# SSPS_Front_Panel_Test.net
KiCad netlist of a schematic drawn in EAGLE
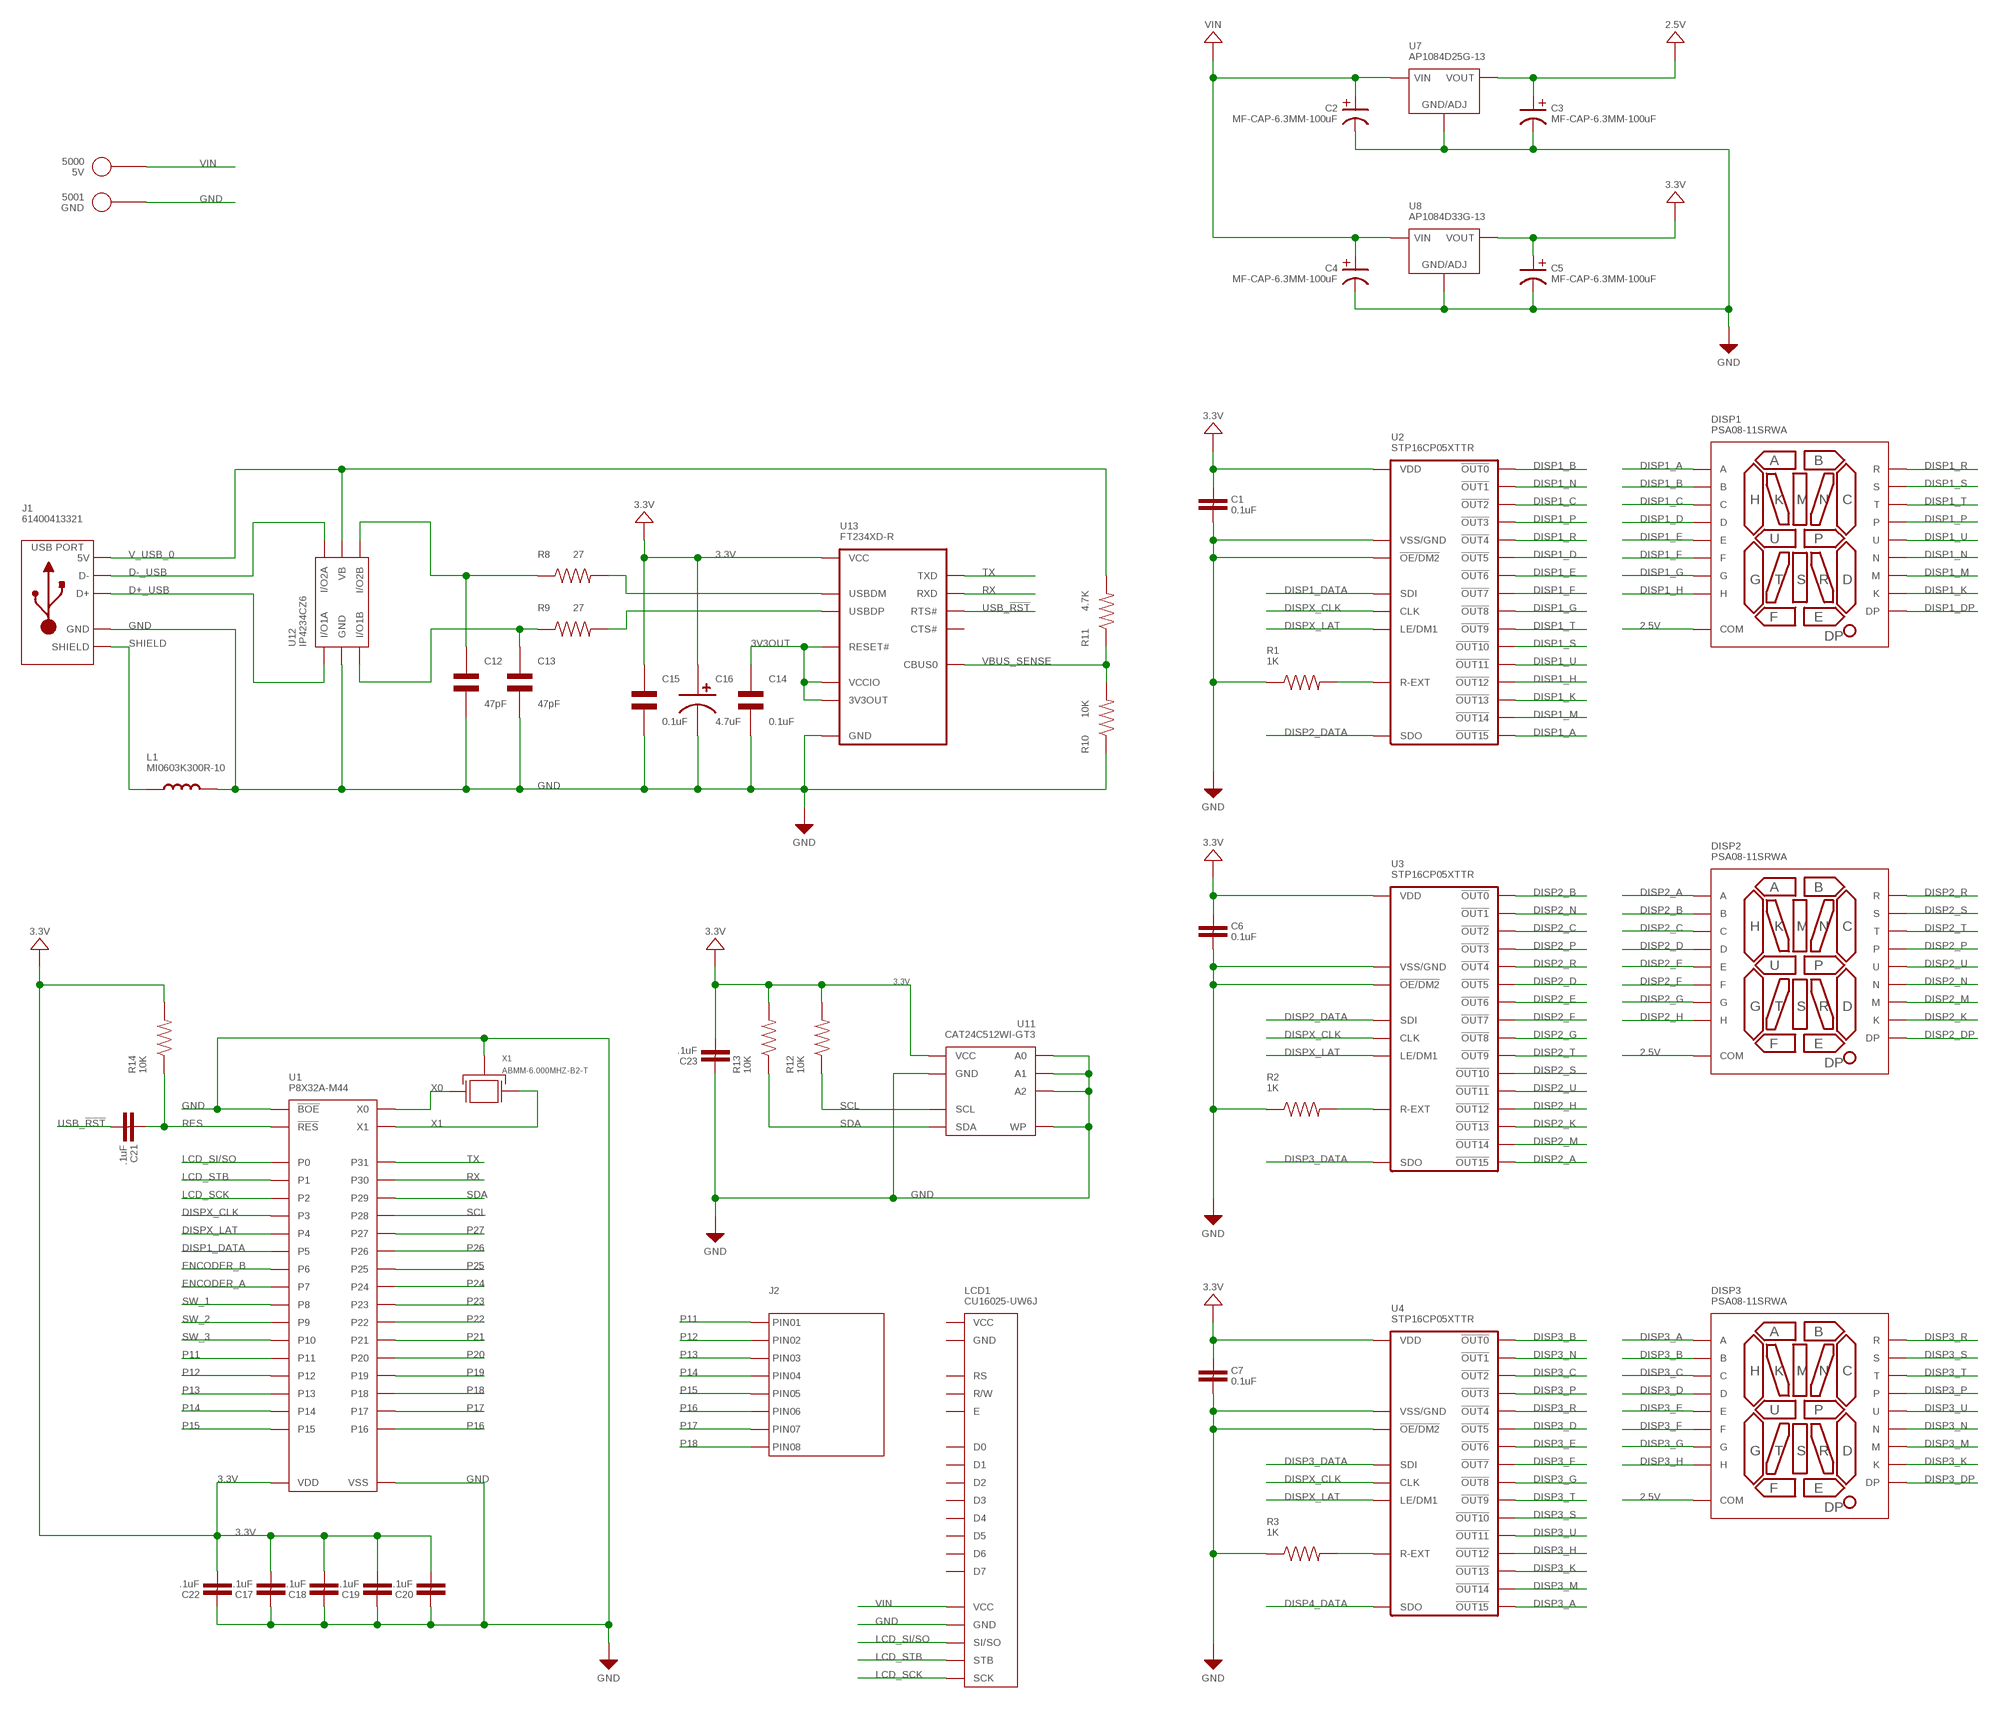
[diagram p0: schematic, sheet 1, part 1 of 3]
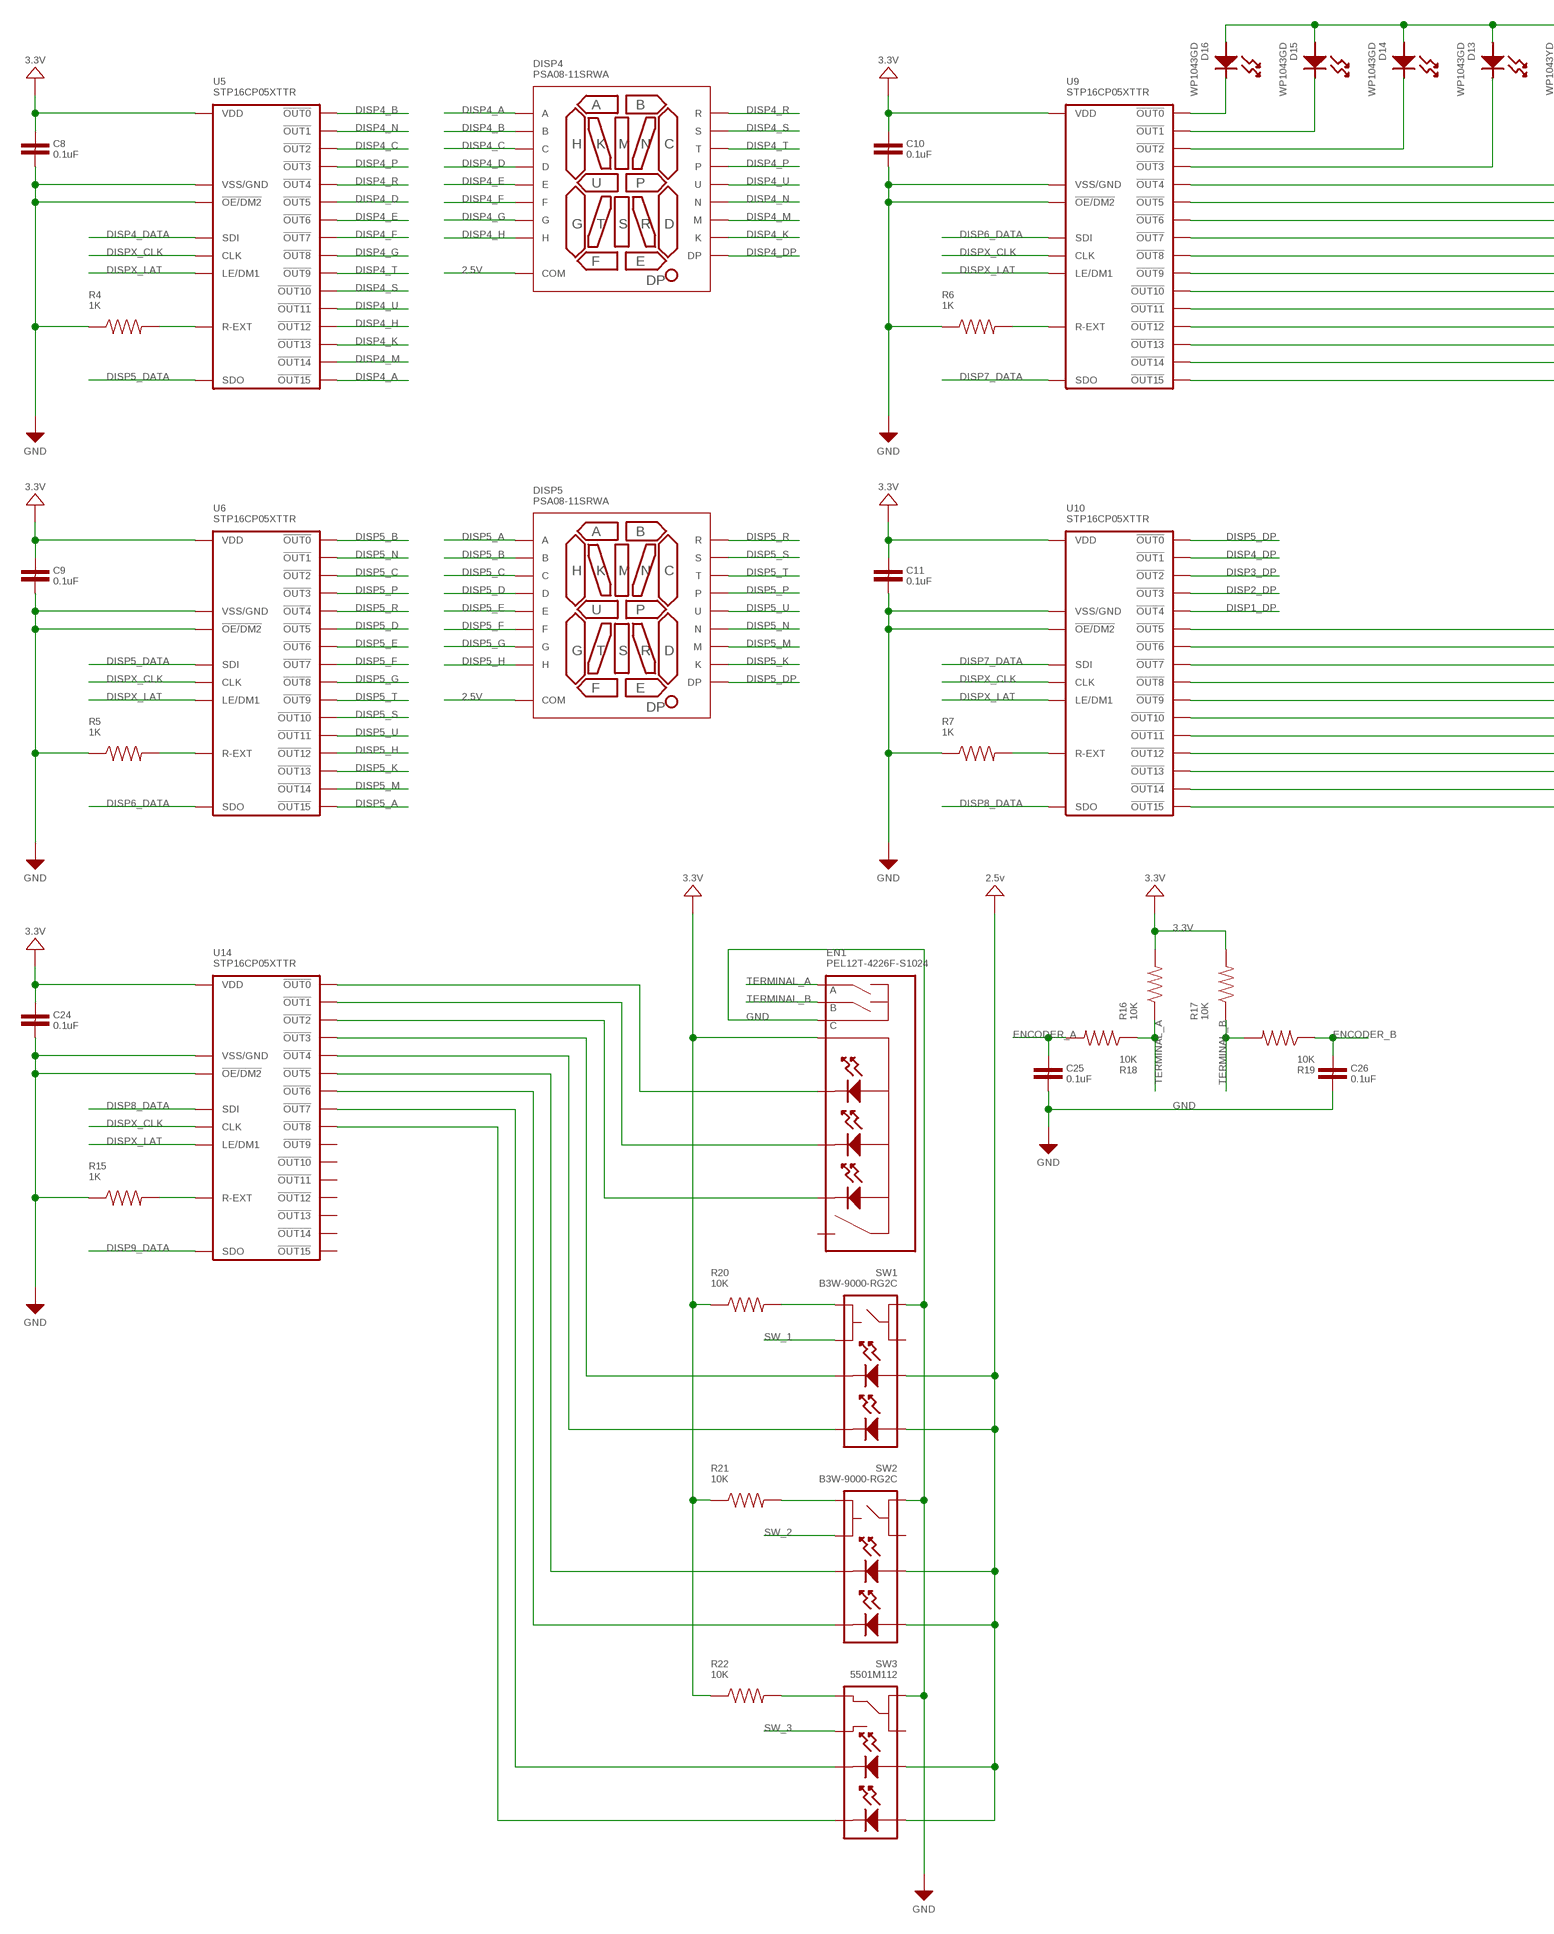
[diagram p1: schematic, sheet 1, part 2 of 3]
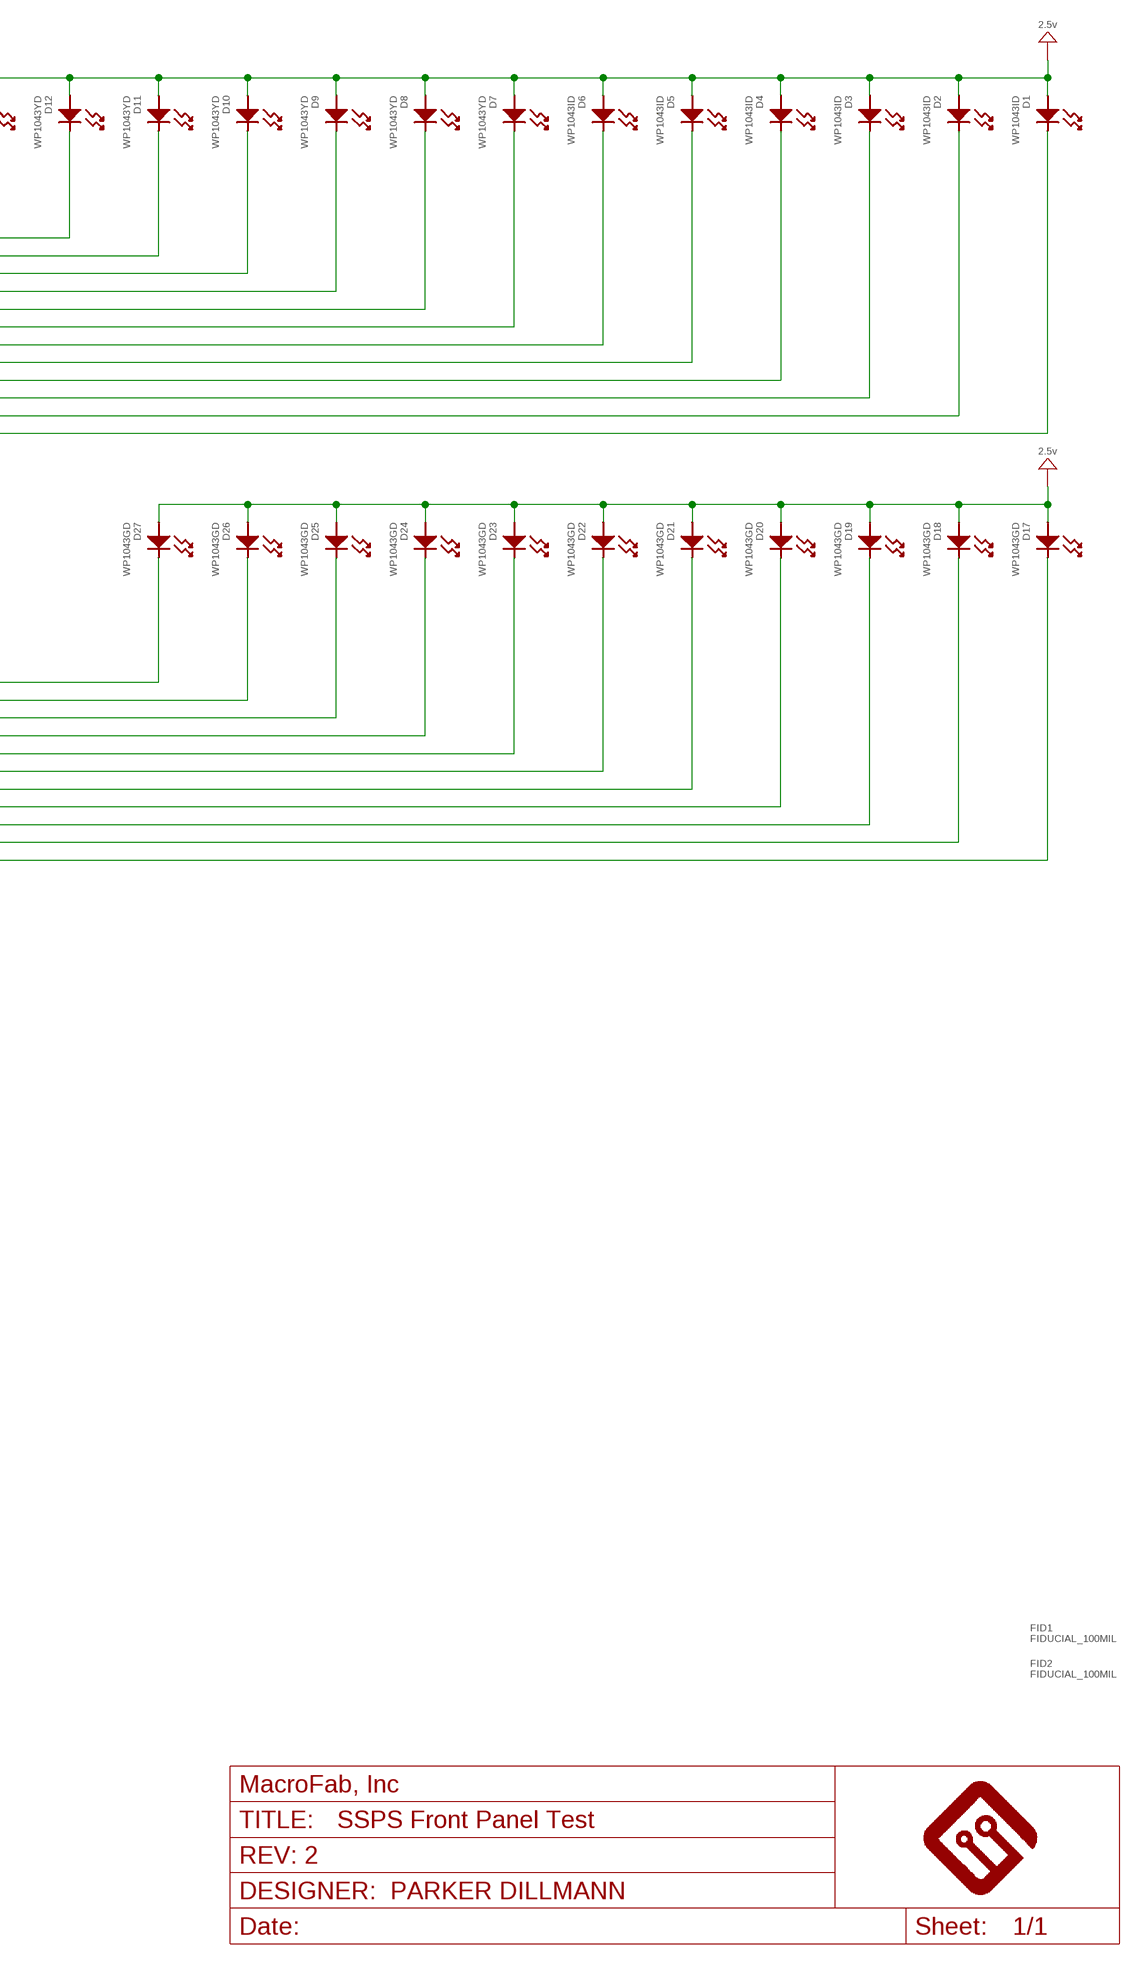
[diagram p2: schematic, sheet 1, part 3 of 3]

(export (version "E")
  (design (tool "Eeschema 10.0.6"))
  (components
    (comp (ref "5V")
      (value "5000")
      (footprint "eagle-import:KEYSTONE_5115-5119")
      (libsource (lib "eagle-import") (part "TEST_POINT_SINGLE_KEYSTONE_5115-5119"))
    )
    (comp (ref "C1")
      (value "0.1uF")
      (footprint "eagle-import:0603")
      (libsource (lib "eagle-import") (part "CAPACITOR_NON_POLAR_0603"))
    )
    (comp (ref "C2")
      (value "MF-CAP-6.3MM-100uF")
      (footprint "eagle-import:6.3MM_CAP_SMD")
      (libsource (lib "eagle-import") (part "CAPACITOR_POLARIZED_6.3MM_SMD"))
    )
    (comp (ref "C3")
      (value "MF-CAP-6.3MM-100uF")
      (footprint "eagle-import:6.3MM_CAP_SMD")
      (libsource (lib "eagle-import") (part "CAPACITOR_POLARIZED_6.3MM_SMD"))
    )
    (comp (ref "C4")
      (value "MF-CAP-6.3MM-100uF")
      (footprint "eagle-import:6.3MM_CAP_SMD")
      (libsource (lib "eagle-import") (part "CAPACITOR_POLARIZED_6.3MM_SMD"))
    )
    (comp (ref "C5")
      (value "MF-CAP-6.3MM-100uF")
      (footprint "eagle-import:6.3MM_CAP_SMD")
      (libsource (lib "eagle-import") (part "CAPACITOR_POLARIZED_6.3MM_SMD"))
    )
    (comp (ref "C6")
      (value "0.1uF")
      (footprint "eagle-import:0603")
      (libsource (lib "eagle-import") (part "CAPACITOR_NON_POLAR_0603"))
    )
    (comp (ref "C7")
      (value "0.1uF")
      (footprint "eagle-import:0603")
      (libsource (lib "eagle-import") (part "CAPACITOR_NON_POLAR_0603"))
    )
    (comp (ref "C8")
      (value "0.1uF")
      (footprint "eagle-import:0603")
      (libsource (lib "eagle-import") (part "CAPACITOR_NON_POLAR_0603"))
    )
    (comp (ref "C9")
      (value "0.1uF")
      (footprint "eagle-import:0603")
      (libsource (lib "eagle-import") (part "CAPACITOR_NON_POLAR_0603"))
    )
    (comp (ref "C10")
      (value "0.1uF")
      (footprint "eagle-import:0603")
      (libsource (lib "eagle-import") (part "CAPACITOR_NON_POLAR_0603"))
    )
    (comp (ref "C11")
      (value "0.1uF")
      (footprint "eagle-import:0603")
      (libsource (lib "eagle-import") (part "CAPACITOR_NON_POLAR_0603"))
    )
    (comp (ref "C12")
      (value "47pF")
      (footprint "eagle-import:C0603")
      (libsource (lib "eagle-import") (part "CAPACITOR_NP_0603"))
    )
    (comp (ref "C13")
      (value "47pF")
      (footprint "eagle-import:C0603")
      (libsource (lib "eagle-import") (part "CAPACITOR_NP_0603"))
    )
    (comp (ref "C14")
      (value "0.1uF")
      (footprint "eagle-import:C0603")
      (libsource (lib "eagle-import") (part "CAPACITOR_NP_0603"))
    )
    (comp (ref "C15")
      (value "0.1uF")
      (footprint "eagle-import:C0603")
      (libsource (lib "eagle-import") (part "CAPACITOR_NP_0603"))
    )
    (comp (ref "C16")
      (value "4.7uF")
      (footprint "eagle-import:CP4MM")
      (libsource (lib "eagle-import") (part "CAPACITOR_P_4MM"))
    )
    (comp (ref "C17")
      (value ".1uF")
      (footprint "eagle-import:0603")
      (libsource (lib "eagle-import") (part "CAPACITOR_NON_POLAR_0603"))
    )
    (comp (ref "C18")
      (value ".1uF")
      (footprint "eagle-import:0603")
      (libsource (lib "eagle-import") (part "CAPACITOR_NON_POLAR_0603"))
    )
    (comp (ref "C19")
      (value ".1uF")
      (footprint "eagle-import:0603")
      (libsource (lib "eagle-import") (part "CAPACITOR_NON_POLAR_0603"))
    )
    (comp (ref "C20")
      (value ".1uF")
      (footprint "eagle-import:0603")
      (libsource (lib "eagle-import") (part "CAPACITOR_NON_POLAR_0603"))
    )
    (comp (ref "C21")
      (value ".1uF")
      (footprint "eagle-import:0603")
      (libsource (lib "eagle-import") (part "CAPACITOR_NON_POLAR_0603"))
    )
    (comp (ref "C22")
      (value ".1uF")
      (footprint "eagle-import:0603")
      (libsource (lib "eagle-import") (part "CAPACITOR_NON_POLAR_0603"))
    )
    (comp (ref "C23")
      (value ".1uF")
      (footprint "eagle-import:0603")
      (libsource (lib "eagle-import") (part "CAPACITOR_NON_POLAR_0603"))
    )
    (comp (ref "C24")
      (value "0.1uF")
      (footprint "eagle-import:0603")
      (libsource (lib "eagle-import") (part "CAPACITOR_NON_POLAR_0603"))
    )
    (comp (ref "C25")
      (value "0.1uF")
      (footprint "eagle-import:0603")
      (libsource (lib "eagle-import") (part "CAPACITOR_NON_POLAR_0603"))
    )
    (comp (ref "C26")
      (value "0.1uF")
      (footprint "eagle-import:0603")
      (libsource (lib "eagle-import") (part "CAPACITOR_NON_POLAR_0603"))
    )
    (comp (ref "D1")
      (value "WP1043ID")
      (footprint "eagle-import:WP1043")
      (libsource (lib "eagle-import") (part "LED_SINGLE_WP1043"))
    )
    (comp (ref "D2")
      (value "WP1043ID")
      (footprint "eagle-import:WP1043")
      (libsource (lib "eagle-import") (part "LED_SINGLE_WP1043"))
    )
    (comp (ref "D3")
      (value "WP1043ID")
      (footprint "eagle-import:WP1043")
      (libsource (lib "eagle-import") (part "LED_SINGLE_WP1043"))
    )
    (comp (ref "D4")
      (value "WP1043ID")
      (footprint "eagle-import:WP1043")
      (libsource (lib "eagle-import") (part "LED_SINGLE_WP1043"))
    )
    (comp (ref "D5")
      (value "WP1043ID")
      (footprint "eagle-import:WP1043")
      (libsource (lib "eagle-import") (part "LED_SINGLE_WP1043"))
    )
    (comp (ref "D6")
      (value "WP1043ID")
      (footprint "eagle-import:WP1043")
      (libsource (lib "eagle-import") (part "LED_SINGLE_WP1043"))
    )
    (comp (ref "D7")
      (value "WP1043YD")
      (footprint "eagle-import:WP1043")
      (libsource (lib "eagle-import") (part "LED_SINGLE_WP1043"))
    )
    (comp (ref "D8")
      (value "WP1043YD")
      (footprint "eagle-import:WP1043")
      (libsource (lib "eagle-import") (part "LED_SINGLE_WP1043"))
    )
    (comp (ref "D9")
      (value "WP1043YD")
      (footprint "eagle-import:WP1043")
      (libsource (lib "eagle-import") (part "LED_SINGLE_WP1043"))
    )
    (comp (ref "D10")
      (value "WP1043YD")
      (footprint "eagle-import:WP1043")
      (libsource (lib "eagle-import") (part "LED_SINGLE_WP1043"))
    )
    (comp (ref "D11")
      (value "WP1043YD")
      (footprint "eagle-import:WP1043")
      (libsource (lib "eagle-import") (part "LED_SINGLE_WP1043"))
    )
    (comp (ref "D12")
      (value "WP1043YD")
      (footprint "eagle-import:WP1043")
      (libsource (lib "eagle-import") (part "LED_SINGLE_WP1043"))
    )
    (comp (ref "D13")
      (value "WP1043GD")
      (footprint "eagle-import:WP1043")
      (libsource (lib "eagle-import") (part "LED_SINGLE_WP1043"))
    )
    (comp (ref "D14")
      (value "WP1043GD")
      (footprint "eagle-import:WP1043")
      (libsource (lib "eagle-import") (part "LED_SINGLE_WP1043"))
    )
    (comp (ref "D15")
      (value "WP1043GD")
      (footprint "eagle-import:WP1043")
      (libsource (lib "eagle-import") (part "LED_SINGLE_WP1043"))
    )
    (comp (ref "D16")
      (value "WP1043GD")
      (footprint "eagle-import:WP1043")
      (libsource (lib "eagle-import") (part "LED_SINGLE_WP1043"))
    )
    (comp (ref "D17")
      (value "WP1043GD")
      (footprint "eagle-import:WP1043")
      (libsource (lib "eagle-import") (part "LED_SINGLE_WP1043"))
    )
    (comp (ref "D18")
      (value "WP1043GD")
      (footprint "eagle-import:WP1043")
      (libsource (lib "eagle-import") (part "LED_SINGLE_WP1043"))
    )
    (comp (ref "D19")
      (value "WP1043GD")
      (footprint "eagle-import:WP1043")
      (libsource (lib "eagle-import") (part "LED_SINGLE_WP1043"))
    )
    (comp (ref "D20")
      (value "WP1043GD")
      (footprint "eagle-import:WP1043")
      (libsource (lib "eagle-import") (part "LED_SINGLE_WP1043"))
    )
    (comp (ref "D21")
      (value "WP1043GD")
      (footprint "eagle-import:WP1043")
      (libsource (lib "eagle-import") (part "LED_SINGLE_WP1043"))
    )
    (comp (ref "D22")
      (value "WP1043GD")
      (footprint "eagle-import:WP1043")
      (libsource (lib "eagle-import") (part "LED_SINGLE_WP1043"))
    )
    (comp (ref "D23")
      (value "WP1043GD")
      (footprint "eagle-import:WP1043")
      (libsource (lib "eagle-import") (part "LED_SINGLE_WP1043"))
    )
    (comp (ref "D24")
      (value "WP1043GD")
      (footprint "eagle-import:WP1043")
      (libsource (lib "eagle-import") (part "LED_SINGLE_WP1043"))
    )
    (comp (ref "D25")
      (value "WP1043GD")
      (footprint "eagle-import:WP1043")
      (libsource (lib "eagle-import") (part "LED_SINGLE_WP1043"))
    )
    (comp (ref "D26")
      (value "WP1043GD")
      (footprint "eagle-import:WP1043")
      (libsource (lib "eagle-import") (part "LED_SINGLE_WP1043"))
    )
    (comp (ref "D27")
      (value "WP1043GD")
      (footprint "eagle-import:WP1043")
      (libsource (lib "eagle-import") (part "LED_SINGLE_WP1043"))
    )
    (comp (ref "DISP1")
      (value "PSA08-11SRWA")
      (footprint "eagle-import:PSA08-11SRWA")
      (libsource (lib "eagle-import") (part "PSA08-11SRWA"))
    )
    (comp (ref "DISP2")
      (value "PSA08-11SRWA")
      (footprint "eagle-import:PSA08-11SRWA")
      (libsource (lib "eagle-import") (part "PSA08-11SRWA"))
    )
    (comp (ref "DISP3")
      (value "PSA08-11SRWA")
      (footprint "eagle-import:PSA08-11SRWA")
      (libsource (lib "eagle-import") (part "PSA08-11SRWA"))
    )
    (comp (ref "DISP4")
      (value "PSA08-11SRWA")
      (footprint "eagle-import:PSA08-11SRWA")
      (libsource (lib "eagle-import") (part "PSA08-11SRWA"))
    )
    (comp (ref "DISP5")
      (value "PSA08-11SRWA")
      (footprint "eagle-import:PSA08-11SRWA")
      (libsource (lib "eagle-import") (part "PSA08-11SRWA"))
    )
    (comp (ref "EN1")
      (value "PEL12T-4226F-S1024")
      (footprint "eagle-import:PEL12T")
      (libsource (lib "eagle-import") (part "PEL12T"))
    )
    (comp (ref "FID1")
      (value "FIDUCIAL_100MIL")
      (footprint "eagle-import:FIDUCIAL_100MIL")
      (libsource (lib "eagle-import") (part "FIDUCIAL_100MIL"))
    )
    (comp (ref "FID2")
      (value "FIDUCIAL_100MIL")
      (footprint "eagle-import:FIDUCIAL_100MIL")
      (libsource (lib "eagle-import") (part "FIDUCIAL_100MIL"))
    )
    (comp (ref "FRAME1")
      (value "MF_FRAMEDEFAULT")
      (footprint "eagle-import:MF_FRAME_DEFAULT")
      (fields (field (name "DNAME") "PARKER DILLMANN") (field (name "REVNUM") "REV: 2"))
      (libsource (lib "eagle-import") (part "MF_FRAMEDEFAULT"))
    )
    (comp (ref "GND")
      (value "5001")
      (footprint "eagle-import:KEYSTONE_5115-5119")
      (libsource (lib "eagle-import") (part "TEST_POINT_SINGLE_KEYSTONE_5115-5119"))
    )
    (comp (ref "J1")
      (value "61400413321")
      (footprint "eagle-import:61400413321")
      (libsource (lib "eagle-import") (part "USB_4PIN_61400413321"))
    )
    (comp (ref "J2")
      (value "CON_01X08_2.54MM_PIN_HEADER")
      (footprint "eagle-import:2.54MM_01X08_PIN_HEADER")
      (libsource (lib "eagle-import") (part "CON_01X08_2.54MM_PIN_HEADER"))
    )
    (comp (ref "L1")
      (value "MI0603K300R-10")
      (footprint "eagle-import:L0603")
      (libsource (lib "eagle-import") (part "INDUCTOR_0603"))
    )
    (comp (ref "LCD1")
      (value "CU16025-UW6J")
      (footprint "eagle-import:CU16025-UW6J")
      (libsource (lib "eagle-import") (part "CU16025-UWJ6"))
    )
    (comp (ref "R1")
      (value "1K")
      (footprint "eagle-import:0603")
      (libsource (lib "eagle-import") (part "PP_Passives_RESISTOR_0603"))
    )
    (comp (ref "R2")
      (value "1K")
      (footprint "eagle-import:0603")
      (libsource (lib "eagle-import") (part "PP_Passives_RESISTOR_0603"))
    )
    (comp (ref "R3")
      (value "1K")
      (footprint "eagle-import:0603")
      (libsource (lib "eagle-import") (part "PP_Passives_RESISTOR_0603"))
    )
    (comp (ref "R4")
      (value "1K")
      (footprint "eagle-import:0603")
      (libsource (lib "eagle-import") (part "PP_Passives_RESISTOR_0603"))
    )
    (comp (ref "R5")
      (value "1K")
      (footprint "eagle-import:0603")
      (libsource (lib "eagle-import") (part "PP_Passives_RESISTOR_0603"))
    )
    (comp (ref "R6")
      (value "1K")
      (footprint "eagle-import:0603")
      (libsource (lib "eagle-import") (part "PP_Passives_RESISTOR_0603"))
    )
    (comp (ref "R7")
      (value "1K")
      (footprint "eagle-import:0603")
      (libsource (lib "eagle-import") (part "PP_Passives_RESISTOR_0603"))
    )
    (comp (ref "R8")
      (value "27")
      (footprint "eagle-import:R0603")
      (libsource (lib "eagle-import") (part "RESISTOR_0603"))
    )
    (comp (ref "R9")
      (value "27")
      (footprint "eagle-import:R0603")
      (libsource (lib "eagle-import") (part "RESISTOR_0603"))
    )
    (comp (ref "R10")
      (value "10K")
      (footprint "eagle-import:R0603")
      (libsource (lib "eagle-import") (part "RESISTOR_0603"))
    )
    (comp (ref "R11")
      (value "4.7K")
      (footprint "eagle-import:R0603")
      (libsource (lib "eagle-import") (part "RESISTOR_0603"))
    )
    (comp (ref "R12")
      (value "10K")
      (footprint "eagle-import:0603")
      (libsource (lib "eagle-import") (part "PP_Passives_RESISTOR_0603"))
    )
    (comp (ref "R13")
      (value "10K")
      (footprint "eagle-import:0603")
      (libsource (lib "eagle-import") (part "PP_Passives_RESISTOR_0603"))
    )
    (comp (ref "R14")
      (value "10K")
      (footprint "eagle-import:0603")
      (libsource (lib "eagle-import") (part "PP_Passives_RESISTOR_0603"))
    )
    (comp (ref "R15")
      (value "1K")
      (footprint "eagle-import:0603")
      (libsource (lib "eagle-import") (part "PP_Passives_RESISTOR_0603"))
    )
    (comp (ref "R16")
      (value "10K")
      (footprint "eagle-import:0603")
      (libsource (lib "eagle-import") (part "PP_Passives_RESISTOR_0603"))
    )
    (comp (ref "R17")
      (value "10K")
      (footprint "eagle-import:0603")
      (libsource (lib "eagle-import") (part "PP_Passives_RESISTOR_0603"))
    )
    (comp (ref "R18")
      (value "10K")
      (footprint "eagle-import:0603")
      (libsource (lib "eagle-import") (part "PP_Passives_RESISTOR_0603"))
    )
    (comp (ref "R19")
      (value "10K")
      (footprint "eagle-import:0603")
      (libsource (lib "eagle-import") (part "PP_Passives_RESISTOR_0603"))
    )
    (comp (ref "R20")
      (value "10K")
      (footprint "eagle-import:0603")
      (libsource (lib "eagle-import") (part "PP_Passives_RESISTOR_0603"))
    )
    (comp (ref "R21")
      (value "10K")
      (footprint "eagle-import:0603")
      (libsource (lib "eagle-import") (part "PP_Passives_RESISTOR_0603"))
    )
    (comp (ref "R22")
      (value "10K")
      (footprint "eagle-import:0603")
      (libsource (lib "eagle-import") (part "PP_Passives_RESISTOR_0603"))
    )
    (comp (ref "SW1")
      (value "B3W-9000-RG2C")
      (footprint "eagle-import:B3W-9000")
      (libsource (lib "eagle-import") (part "B3W-9000"))
    )
    (comp (ref "SW2")
      (value "B3W-9000-RG2C")
      (footprint "eagle-import:B3W-9000")
      (libsource (lib "eagle-import") (part "B3W-9000"))
    )
    (comp (ref "SW3")
      (value "5501M112")
      (footprint "eagle-import:5501")
      (libsource (lib "eagle-import") (part "5501"))
    )
    (comp (ref "U1")
      (value "P8X32A-M44")
      (footprint "eagle-import:P8X32A_QFN-44")
      (libsource (lib "eagle-import") (part "P8X32A-M44"))
    )
    (comp (ref "U2")
      (value "STP16CP05XTTR")
      (footprint "eagle-import:STP16CP05XTTR_TTSOP-24")
      (libsource (lib "eagle-import") (part "STP16CP05XTTR"))
    )
    (comp (ref "U3")
      (value "STP16CP05XTTR")
      (footprint "eagle-import:STP16CP05XTTR_TTSOP-24")
      (libsource (lib "eagle-import") (part "STP16CP05XTTR"))
    )
    (comp (ref "U4")
      (value "STP16CP05XTTR")
      (footprint "eagle-import:STP16CP05XTTR_TTSOP-24")
      (libsource (lib "eagle-import") (part "STP16CP05XTTR"))
    )
    (comp (ref "U5")
      (value "STP16CP05XTTR")
      (footprint "eagle-import:STP16CP05XTTR_TTSOP-24")
      (libsource (lib "eagle-import") (part "STP16CP05XTTR"))
    )
    (comp (ref "U6")
      (value "STP16CP05XTTR")
      (footprint "eagle-import:STP16CP05XTTR_TTSOP-24")
      (libsource (lib "eagle-import") (part "STP16CP05XTTR"))
    )
    (comp (ref "U7")
      (value "AP1084D25G-13")
      (footprint "eagle-import:AP1084_TO-252-3L")
      (libsource (lib "eagle-import") (part "LINEAR_VOTLAGE_REGULATORS_AP1084"))
    )
    (comp (ref "U8")
      (value "AP1084D33G-13")
      (footprint "eagle-import:AP1084_TO-252-3L")
      (libsource (lib "eagle-import") (part "LINEAR_VOTLAGE_REGULATORS_AP1084"))
    )
    (comp (ref "U9")
      (value "STP16CP05XTTR")
      (footprint "eagle-import:STP16CP05XTTR_TTSOP-24")
      (libsource (lib "eagle-import") (part "STP16CP05XTTR"))
    )
    (comp (ref "U10")
      (value "STP16CP05XTTR")
      (footprint "eagle-import:STP16CP05XTTR_TTSOP-24")
      (libsource (lib "eagle-import") (part "STP16CP05XTTR"))
    )
    (comp (ref "U11")
      (value "CAT24C512WI-GT3")
      (footprint "eagle-import:SOIC-8_W")
      (libsource (lib "eagle-import") (part "EEPROM_I2CSOIC-8_W"))
    )
    (comp (ref "U12")
      (value "IP4234CZ6")
      (footprint "eagle-import:IP4234CZ6_SOT-457-6")
      (libsource (lib "eagle-import") (part "IP4234CZ6"))
    )
    (comp (ref "U13")
      (value "FT234XD-R")
      (footprint "eagle-import:FT234X_DFN-12")
      (libsource (lib "eagle-import") (part "FT234XD"))
    )
    (comp (ref "U14")
      (value "STP16CP05XTTR")
      (footprint "eagle-import:STP16CP05XTTR_TTSOP-24")
      (libsource (lib "eagle-import") (part "STP16CP05XTTR"))
    )
    (comp (ref "X1")
      (value "ABMM-6.000MHZ-B2-T")
      (footprint "eagle-import:7MMX5MM")
      (libsource (lib "eagle-import") (part "XTL_7MMX5MM"))
    )
  )
  (nets
    (net (code "1") (name "/3V3OUT") (class "Default")
      (node (ref "C14") (pin "P$1") (pinfunction "P$1_P$1") (pintype "passive"))
      (node (ref "U13") (pin "2") (pinfunction "RESET#_2") (pintype "bidirectional"))
      (node (ref "U13") (pin "3") (pinfunction "3V3OUT_3") (pintype "bidirectional"))
      (node (ref "U13") (pin "9") (pinfunction "VCCIO_9") (pintype "bidirectional"))
    )
    (net (code "2") (name "/D+_USB") (class "Default")
      (node (ref "J1") (pin "3") (pinfunction "D+_3") (pintype "bidirectional"))
      (node (ref "U12") (pin "1") (pinfunction "I/O1A_1") (pintype "bidirectional"))
    )
    (net (code "3") (name "/D-_USB") (class "Default")
      (node (ref "J1") (pin "2") (pinfunction "D-_2") (pintype "bidirectional"))
      (node (ref "U12") (pin "6") (pinfunction "I/O2A_6") (pintype "bidirectional"))
    )
    (net (code "4") (name "/DISP1_A") (class "Default")
      (node (ref "DISP1") (pin "P$1") (pinfunction "A_P$1") (pintype "bidirectional"))
      (node (ref "U2") (pin "P$20") (pinfunction "~{OUT15}_P$20") (pintype "bidirectional"))
    )
    (net (code "5") (name "/DISP1_B") (class "Default")
      (node (ref "DISP1") (pin "P$18") (pinfunction "B_P$18") (pintype "bidirectional"))
      (node (ref "U2") (pin "P$5") (pinfunction "~{OUT0}_P$5") (pintype "bidirectional"))
    )
    (net (code "6") (name "/DISP1_C") (class "Default")
      (node (ref "DISP1") (pin "P$16") (pinfunction "C_P$16") (pintype "bidirectional"))
      (node (ref "U2") (pin "P$7") (pinfunction "~{OUT2}_P$7") (pintype "bidirectional"))
    )
    (net (code "7") (name "/DISP1_D") (class "Default")
      (node (ref "DISP1") (pin "P$13") (pinfunction "D_P$13") (pintype "bidirectional"))
      (node (ref "U2") (pin "P$10") (pinfunction "~{OUT5}_P$10") (pintype "bidirectional"))
    )
    (net (code "8") (name "/DISP1_DATA") (class "Default")
      (node (ref "U1") (pin "2") (pinfunction "P5_2") (pintype "bidirectional"))
      (node (ref "U2") (pin "P$2") (pinfunction "SDI_P$2") (pintype "bidirectional"))
    )
    (net (code "9") (name "/DISP1_DP") (class "Default")
      (node (ref "DISP1") (pin "P$12") (pinfunction "DP_P$12") (pintype "bidirectional"))
      (node (ref "U10") (pin "P$9") (pinfunction "~{OUT4}_P$9") (pintype "bidirectional"))
    )
    (net (code "10") (name "/DISP1_E") (class "Default")
      (node (ref "DISP1") (pin "P$10") (pinfunction "E_P$10") (pintype "bidirectional"))
      (node (ref "U2") (pin "P$11") (pinfunction "~{OUT6}_P$11") (pintype "bidirectional"))
    )
    (net (code "11") (name "/DISP1_F") (class "Default")
      (node (ref "DISP1") (pin "P$9") (pinfunction "F_P$9") (pintype "bidirectional"))
      (node (ref "U2") (pin "P$12") (pinfunction "~{OUT7}_P$12") (pintype "bidirectional"))
    )
    (net (code "12") (name "/DISP1_G") (class "Default")
      (node (ref "DISP1") (pin "P$8") (pinfunction "G_P$8") (pintype "bidirectional"))
      (node (ref "U2") (pin "P$13") (pinfunction "~{OUT8}_P$13") (pintype "bidirectional"))
    )
    (net (code "13") (name "/DISP1_H") (class "Default")
      (node (ref "DISP1") (pin "P$4") (pinfunction "H_P$4") (pintype "bidirectional"))
      (node (ref "U2") (pin "P$17") (pinfunction "~{OUT12}_P$17") (pintype "bidirectional"))
    )
    (net (code "14") (name "/DISP1_K") (class "Default")
      (node (ref "DISP1") (pin "P$3") (pinfunction "K_P$3") (pintype "bidirectional"))
      (node (ref "U2") (pin "P$18") (pinfunction "~{OUT13}_P$18") (pintype "bidirectional"))
    )
    (net (code "15") (name "/DISP1_M") (class "Default")
      (node (ref "DISP1") (pin "P$2") (pinfunction "M_P$2") (pintype "bidirectional"))
      (node (ref "U2") (pin "P$19") (pinfunction "~{OUT14}_P$19") (pintype "bidirectional"))
    )
    (net (code "16") (name "/DISP1_N") (class "Default")
      (node (ref "DISP1") (pin "P$17") (pinfunction "N_P$17") (pintype "bidirectional"))
      (node (ref "U2") (pin "P$6") (pinfunction "~{OUT1}_P$6") (pintype "bidirectional"))
    )
    (net (code "17") (name "/DISP1_P") (class "Default")
      (node (ref "DISP1") (pin "P$15") (pinfunction "P_P$15") (pintype "bidirectional"))
      (node (ref "U2") (pin "P$8") (pinfunction "~{OUT3}_P$8") (pintype "bidirectional"))
    )
    (net (code "18") (name "/DISP1_R") (class "Default")
      (node (ref "DISP1") (pin "P$14") (pinfunction "R_P$14") (pintype "bidirectional"))
      (node (ref "U2") (pin "P$9") (pinfunction "~{OUT4}_P$9") (pintype "bidirectional"))
    )
    (net (code "19") (name "/DISP1_S") (class "Default")
      (node (ref "DISP1") (pin "P$6") (pinfunction "S_P$6") (pintype "bidirectional"))
      (node (ref "U2") (pin "P$15") (pinfunction "~{OUT10}_P$15") (pintype "bidirectional"))
    )
    (net (code "20") (name "/DISP1_T") (class "Default")
      (node (ref "DISP1") (pin "P$7") (pinfunction "T_P$7") (pintype "bidirectional"))
      (node (ref "U2") (pin "P$14") (pinfunction "~{OUT9}_P$14") (pintype "bidirectional"))
    )
    (net (code "21") (name "/DISP1_U") (class "Default")
      (node (ref "DISP1") (pin "P$5") (pinfunction "U_P$5") (pintype "bidirectional"))
      (node (ref "U2") (pin "P$16") (pinfunction "~{OUT11}_P$16") (pintype "bidirectional"))
    )
    (net (code "22") (name "/DISP2_A") (class "Default")
      (node (ref "DISP2") (pin "P$1") (pinfunction "A_P$1") (pintype "bidirectional"))
      (node (ref "U3") (pin "P$20") (pinfunction "~{OUT15}_P$20") (pintype "bidirectional"))
    )
    (net (code "23") (name "/DISP2_B") (class "Default")
      (node (ref "DISP2") (pin "P$18") (pinfunction "B_P$18") (pintype "bidirectional"))
      (node (ref "U3") (pin "P$5") (pinfunction "~{OUT0}_P$5") (pintype "bidirectional"))
    )
    (net (code "24") (name "/DISP2_C") (class "Default")
      (node (ref "DISP2") (pin "P$16") (pinfunction "C_P$16") (pintype "bidirectional"))
      (node (ref "U3") (pin "P$7") (pinfunction "~{OUT2}_P$7") (pintype "bidirectional"))
    )
    (net (code "25") (name "/DISP2_D") (class "Default")
      (node (ref "DISP2") (pin "P$13") (pinfunction "D_P$13") (pintype "bidirectional"))
      (node (ref "U3") (pin "P$10") (pinfunction "~{OUT5}_P$10") (pintype "bidirectional"))
    )
    (net (code "26") (name "/DISP2_DATA") (class "Default")
      (node (ref "U2") (pin "P$22") (pinfunction "SDO_P$22") (pintype "bidirectional"))
      (node (ref "U3") (pin "P$2") (pinfunction "SDI_P$2") (pintype "bidirectional"))
    )
    (net (code "27") (name "/DISP2_DP") (class "Default")
      (node (ref "DISP2") (pin "P$12") (pinfunction "DP_P$12") (pintype "bidirectional"))
      (node (ref "U10") (pin "P$8") (pinfunction "~{OUT3}_P$8") (pintype "bidirectional"))
    )
    (net (code "28") (name "/DISP2_E") (class "Default")
      (node (ref "DISP2") (pin "P$10") (pinfunction "E_P$10") (pintype "bidirectional"))
      (node (ref "U3") (pin "P$11") (pinfunction "~{OUT6}_P$11") (pintype "bidirectional"))
    )
    (net (code "29") (name "/DISP2_F") (class "Default")
      (node (ref "DISP2") (pin "P$9") (pinfunction "F_P$9") (pintype "bidirectional"))
      (node (ref "U3") (pin "P$12") (pinfunction "~{OUT7}_P$12") (pintype "bidirectional"))
    )
    (net (code "30") (name "/DISP2_G") (class "Default")
      (node (ref "DISP2") (pin "P$8") (pinfunction "G_P$8") (pintype "bidirectional"))
      (node (ref "U3") (pin "P$13") (pinfunction "~{OUT8}_P$13") (pintype "bidirectional"))
    )
    (net (code "31") (name "/DISP2_H") (class "Default")
      (node (ref "DISP2") (pin "P$4") (pinfunction "H_P$4") (pintype "bidirectional"))
      (node (ref "U3") (pin "P$17") (pinfunction "~{OUT12}_P$17") (pintype "bidirectional"))
    )
    (net (code "32") (name "/DISP2_K") (class "Default")
      (node (ref "DISP2") (pin "P$3") (pinfunction "K_P$3") (pintype "bidirectional"))
      (node (ref "U3") (pin "P$18") (pinfunction "~{OUT13}_P$18") (pintype "bidirectional"))
    )
    (net (code "33") (name "/DISP2_M") (class "Default")
      (node (ref "DISP2") (pin "P$2") (pinfunction "M_P$2") (pintype "bidirectional"))
      (node (ref "U3") (pin "P$19") (pinfunction "~{OUT14}_P$19") (pintype "bidirectional"))
    )
    (net (code "34") (name "/DISP2_N") (class "Default")
      (node (ref "DISP2") (pin "P$17") (pinfunction "N_P$17") (pintype "bidirectional"))
      (node (ref "U3") (pin "P$6") (pinfunction "~{OUT1}_P$6") (pintype "bidirectional"))
    )
    (net (code "35") (name "/DISP2_P") (class "Default")
      (node (ref "DISP2") (pin "P$15") (pinfunction "P_P$15") (pintype "bidirectional"))
      (node (ref "U3") (pin "P$8") (pinfunction "~{OUT3}_P$8") (pintype "bidirectional"))
    )
    (net (code "36") (name "/DISP2_R") (class "Default")
      (node (ref "DISP2") (pin "P$14") (pinfunction "R_P$14") (pintype "bidirectional"))
      (node (ref "U3") (pin "P$9") (pinfunction "~{OUT4}_P$9") (pintype "bidirectional"))
    )
    (net (code "37") (name "/DISP2_S") (class "Default")
      (node (ref "DISP2") (pin "P$6") (pinfunction "S_P$6") (pintype "bidirectional"))
      (node (ref "U3") (pin "P$15") (pinfunction "~{OUT10}_P$15") (pintype "bidirectional"))
    )
    (net (code "38") (name "/DISP2_T") (class "Default")
      (node (ref "DISP2") (pin "P$7") (pinfunction "T_P$7") (pintype "bidirectional"))
      (node (ref "U3") (pin "P$14") (pinfunction "~{OUT9}_P$14") (pintype "bidirectional"))
    )
    (net (code "39") (name "/DISP2_U") (class "Default")
      (node (ref "DISP2") (pin "P$5") (pinfunction "U_P$5") (pintype "bidirectional"))
      (node (ref "U3") (pin "P$16") (pinfunction "~{OUT11}_P$16") (pintype "bidirectional"))
    )
    (net (code "40") (name "/DISP3_A") (class "Default")
      (node (ref "DISP3") (pin "P$1") (pinfunction "A_P$1") (pintype "bidirectional"))
      (node (ref "U4") (pin "P$20") (pinfunction "~{OUT15}_P$20") (pintype "bidirectional"))
    )
    (net (code "41") (name "/DISP3_B") (class "Default")
      (node (ref "DISP3") (pin "P$18") (pinfunction "B_P$18") (pintype "bidirectional"))
      (node (ref "U4") (pin "P$5") (pinfunction "~{OUT0}_P$5") (pintype "bidirectional"))
    )
    (net (code "42") (name "/DISP3_C") (class "Default")
      (node (ref "DISP3") (pin "P$16") (pinfunction "C_P$16") (pintype "bidirectional"))
      (node (ref "U4") (pin "P$7") (pinfunction "~{OUT2}_P$7") (pintype "bidirectional"))
    )
    (net (code "43") (name "/DISP3_D") (class "Default")
      (node (ref "DISP3") (pin "P$13") (pinfunction "D_P$13") (pintype "bidirectional"))
      (node (ref "U4") (pin "P$10") (pinfunction "~{OUT5}_P$10") (pintype "bidirectional"))
    )
    (net (code "44") (name "/DISP3_DATA") (class "Default")
      (node (ref "U3") (pin "P$22") (pinfunction "SDO_P$22") (pintype "bidirectional"))
      (node (ref "U4") (pin "P$2") (pinfunction "SDI_P$2") (pintype "bidirectional"))
    )
    (net (code "45") (name "/DISP3_DP") (class "Default")
      (node (ref "DISP3") (pin "P$12") (pinfunction "DP_P$12") (pintype "bidirectional"))
      (node (ref "U10") (pin "P$7") (pinfunction "~{OUT2}_P$7") (pintype "bidirectional"))
    )
    (net (code "46") (name "/DISP3_E") (class "Default")
      (node (ref "DISP3") (pin "P$10") (pinfunction "E_P$10") (pintype "bidirectional"))
      (node (ref "U4") (pin "P$11") (pinfunction "~{OUT6}_P$11") (pintype "bidirectional"))
    )
    (net (code "47") (name "/DISP3_F") (class "Default")
      (node (ref "DISP3") (pin "P$9") (pinfunction "F_P$9") (pintype "bidirectional"))
      (node (ref "U4") (pin "P$12") (pinfunction "~{OUT7}_P$12") (pintype "bidirectional"))
    )
    (net (code "48") (name "/DISP3_G") (class "Default")
      (node (ref "DISP3") (pin "P$8") (pinfunction "G_P$8") (pintype "bidirectional"))
      (node (ref "U4") (pin "P$13") (pinfunction "~{OUT8}_P$13") (pintype "bidirectional"))
    )
    (net (code "49") (name "/DISP3_H") (class "Default")
      (node (ref "DISP3") (pin "P$4") (pinfunction "H_P$4") (pintype "bidirectional"))
      (node (ref "U4") (pin "P$17") (pinfunction "~{OUT12}_P$17") (pintype "bidirectional"))
    )
    (net (code "50") (name "/DISP3_K") (class "Default")
      (node (ref "DISP3") (pin "P$3") (pinfunction "K_P$3") (pintype "bidirectional"))
      (node (ref "U4") (pin "P$18") (pinfunction "~{OUT13}_P$18") (pintype "bidirectional"))
    )
    (net (code "51") (name "/DISP3_M") (class "Default")
      (node (ref "DISP3") (pin "P$2") (pinfunction "M_P$2") (pintype "bidirectional"))
      (node (ref "U4") (pin "P$19") (pinfunction "~{OUT14}_P$19") (pintype "bidirectional"))
    )
    (net (code "52") (name "/DISP3_N") (class "Default")
      (node (ref "DISP3") (pin "P$17") (pinfunction "N_P$17") (pintype "bidirectional"))
      (node (ref "U4") (pin "P$6") (pinfunction "~{OUT1}_P$6") (pintype "bidirectional"))
    )
    (net (code "53") (name "/DISP3_P") (class "Default")
      (node (ref "DISP3") (pin "P$15") (pinfunction "P_P$15") (pintype "bidirectional"))
      (node (ref "U4") (pin "P$8") (pinfunction "~{OUT3}_P$8") (pintype "bidirectional"))
    )
    (net (code "54") (name "/DISP3_R") (class "Default")
      (node (ref "DISP3") (pin "P$14") (pinfunction "R_P$14") (pintype "bidirectional"))
      (node (ref "U4") (pin "P$9") (pinfunction "~{OUT4}_P$9") (pintype "bidirectional"))
    )
    (net (code "55") (name "/DISP3_S") (class "Default")
      (node (ref "DISP3") (pin "P$6") (pinfunction "S_P$6") (pintype "bidirectional"))
      (node (ref "U4") (pin "P$15") (pinfunction "~{OUT10}_P$15") (pintype "bidirectional"))
    )
    (net (code "56") (name "/DISP3_T") (class "Default")
      (node (ref "DISP3") (pin "P$7") (pinfunction "T_P$7") (pintype "bidirectional"))
      (node (ref "U4") (pin "P$14") (pinfunction "~{OUT9}_P$14") (pintype "bidirectional"))
    )
    (net (code "57") (name "/DISP3_U") (class "Default")
      (node (ref "DISP3") (pin "P$5") (pinfunction "U_P$5") (pintype "bidirectional"))
      (node (ref "U4") (pin "P$16") (pinfunction "~{OUT11}_P$16") (pintype "bidirectional"))
    )
    (net (code "58") (name "/DISP4_A") (class "Default")
      (node (ref "DISP4") (pin "P$1") (pinfunction "A_P$1") (pintype "bidirectional"))
      (node (ref "U5") (pin "P$20") (pinfunction "~{OUT15}_P$20") (pintype "bidirectional"))
    )
    (net (code "59") (name "/DISP4_B") (class "Default")
      (node (ref "DISP4") (pin "P$18") (pinfunction "B_P$18") (pintype "bidirectional"))
      (node (ref "U5") (pin "P$5") (pinfunction "~{OUT0}_P$5") (pintype "bidirectional"))
    )
    (net (code "60") (name "/DISP4_C") (class "Default")
      (node (ref "DISP4") (pin "P$16") (pinfunction "C_P$16") (pintype "bidirectional"))
      (node (ref "U5") (pin "P$7") (pinfunction "~{OUT2}_P$7") (pintype "bidirectional"))
    )
    (net (code "61") (name "/DISP4_D") (class "Default")
      (node (ref "DISP4") (pin "P$13") (pinfunction "D_P$13") (pintype "bidirectional"))
      (node (ref "U5") (pin "P$10") (pinfunction "~{OUT5}_P$10") (pintype "bidirectional"))
    )
    (net (code "62") (name "/DISP4_DATA") (class "Default")
      (node (ref "U4") (pin "P$22") (pinfunction "SDO_P$22") (pintype "bidirectional"))
      (node (ref "U5") (pin "P$2") (pinfunction "SDI_P$2") (pintype "bidirectional"))
    )
    (net (code "63") (name "/DISP4_DP") (class "Default")
      (node (ref "DISP4") (pin "P$12") (pinfunction "DP_P$12") (pintype "bidirectional"))
      (node (ref "U10") (pin "P$6") (pinfunction "~{OUT1}_P$6") (pintype "bidirectional"))
    )
    (net (code "64") (name "/DISP4_E") (class "Default")
      (node (ref "DISP4") (pin "P$10") (pinfunction "E_P$10") (pintype "bidirectional"))
      (node (ref "U5") (pin "P$11") (pinfunction "~{OUT6}_P$11") (pintype "bidirectional"))
    )
    (net (code "65") (name "/DISP4_F") (class "Default")
      (node (ref "DISP4") (pin "P$9") (pinfunction "F_P$9") (pintype "bidirectional"))
      (node (ref "U5") (pin "P$12") (pinfunction "~{OUT7}_P$12") (pintype "bidirectional"))
    )
    (net (code "66") (name "/DISP4_G") (class "Default")
      (node (ref "DISP4") (pin "P$8") (pinfunction "G_P$8") (pintype "bidirectional"))
      (node (ref "U5") (pin "P$13") (pinfunction "~{OUT8}_P$13") (pintype "bidirectional"))
    )
    (net (code "67") (name "/DISP4_H") (class "Default")
      (node (ref "DISP4") (pin "P$4") (pinfunction "H_P$4") (pintype "bidirectional"))
      (node (ref "U5") (pin "P$17") (pinfunction "~{OUT12}_P$17") (pintype "bidirectional"))
    )
    (net (code "68") (name "/DISP4_K") (class "Default")
      (node (ref "DISP4") (pin "P$3") (pinfunction "K_P$3") (pintype "bidirectional"))
      (node (ref "U5") (pin "P$18") (pinfunction "~{OUT13}_P$18") (pintype "bidirectional"))
    )
    (net (code "69") (name "/DISP4_M") (class "Default")
      (node (ref "DISP4") (pin "P$2") (pinfunction "M_P$2") (pintype "bidirectional"))
      (node (ref "U5") (pin "P$19") (pinfunction "~{OUT14}_P$19") (pintype "bidirectional"))
    )
    (net (code "70") (name "/DISP4_N") (class "Default")
      (node (ref "DISP4") (pin "P$17") (pinfunction "N_P$17") (pintype "bidirectional"))
      (node (ref "U5") (pin "P$6") (pinfunction "~{OUT1}_P$6") (pintype "bidirectional"))
    )
    (net (code "71") (name "/DISP4_P") (class "Default")
      (node (ref "DISP4") (pin "P$15") (pinfunction "P_P$15") (pintype "bidirectional"))
      (node (ref "U5") (pin "P$8") (pinfunction "~{OUT3}_P$8") (pintype "bidirectional"))
    )
    (net (code "72") (name "/DISP4_R") (class "Default")
      (node (ref "DISP4") (pin "P$14") (pinfunction "R_P$14") (pintype "bidirectional"))
      (node (ref "U5") (pin "P$9") (pinfunction "~{OUT4}_P$9") (pintype "bidirectional"))
    )
    (net (code "73") (name "/DISP4_S") (class "Default")
      (node (ref "DISP4") (pin "P$6") (pinfunction "S_P$6") (pintype "bidirectional"))
      (node (ref "U5") (pin "P$15") (pinfunction "~{OUT10}_P$15") (pintype "bidirectional"))
    )
    (net (code "74") (name "/DISP4_T") (class "Default")
      (node (ref "DISP4") (pin "P$7") (pinfunction "T_P$7") (pintype "bidirectional"))
      (node (ref "U5") (pin "P$14") (pinfunction "~{OUT9}_P$14") (pintype "bidirectional"))
    )
    (net (code "75") (name "/DISP4_U") (class "Default")
      (node (ref "DISP4") (pin "P$5") (pinfunction "U_P$5") (pintype "bidirectional"))
      (node (ref "U5") (pin "P$16") (pinfunction "~{OUT11}_P$16") (pintype "bidirectional"))
    )
    (net (code "76") (name "/DISP5_A") (class "Default")
      (node (ref "DISP5") (pin "P$1") (pinfunction "A_P$1") (pintype "bidirectional"))
      (node (ref "U6") (pin "P$20") (pinfunction "~{OUT15}_P$20") (pintype "bidirectional"))
    )
    (net (code "77") (name "/DISP5_B") (class "Default")
      (node (ref "DISP5") (pin "P$18") (pinfunction "B_P$18") (pintype "bidirectional"))
      (node (ref "U6") (pin "P$5") (pinfunction "~{OUT0}_P$5") (pintype "bidirectional"))
    )
    (net (code "78") (name "/DISP5_C") (class "Default")
      (node (ref "DISP5") (pin "P$16") (pinfunction "C_P$16") (pintype "bidirectional"))
      (node (ref "U6") (pin "P$7") (pinfunction "~{OUT2}_P$7") (pintype "bidirectional"))
    )
    (net (code "79") (name "/DISP5_D") (class "Default")
      (node (ref "DISP5") (pin "P$13") (pinfunction "D_P$13") (pintype "bidirectional"))
      (node (ref "U6") (pin "P$10") (pinfunction "~{OUT5}_P$10") (pintype "bidirectional"))
    )
    (net (code "80") (name "/DISP5_DATA") (class "Default")
      (node (ref "U5") (pin "P$22") (pinfunction "SDO_P$22") (pintype "bidirectional"))
      (node (ref "U6") (pin "P$2") (pinfunction "SDI_P$2") (pintype "bidirectional"))
    )
    (net (code "81") (name "/DISP5_DP") (class "Default")
      (node (ref "DISP5") (pin "P$12") (pinfunction "DP_P$12") (pintype "bidirectional"))
      (node (ref "U10") (pin "P$5") (pinfunction "~{OUT0}_P$5") (pintype "bidirectional"))
    )
    (net (code "82") (name "/DISP5_E") (class "Default")
      (node (ref "DISP5") (pin "P$10") (pinfunction "E_P$10") (pintype "bidirectional"))
      (node (ref "U6") (pin "P$11") (pinfunction "~{OUT6}_P$11") (pintype "bidirectional"))
    )
    (net (code "83") (name "/DISP5_F") (class "Default")
      (node (ref "DISP5") (pin "P$9") (pinfunction "F_P$9") (pintype "bidirectional"))
      (node (ref "U6") (pin "P$12") (pinfunction "~{OUT7}_P$12") (pintype "bidirectional"))
    )
    (net (code "84") (name "/DISP5_G") (class "Default")
      (node (ref "DISP5") (pin "P$8") (pinfunction "G_P$8") (pintype "bidirectional"))
      (node (ref "U6") (pin "P$13") (pinfunction "~{OUT8}_P$13") (pintype "bidirectional"))
    )
    (net (code "85") (name "/DISP5_H") (class "Default")
      (node (ref "DISP5") (pin "P$4") (pinfunction "H_P$4") (pintype "bidirectional"))
      (node (ref "U6") (pin "P$17") (pinfunction "~{OUT12}_P$17") (pintype "bidirectional"))
    )
    (net (code "86") (name "/DISP5_K") (class "Default")
      (node (ref "DISP5") (pin "P$3") (pinfunction "K_P$3") (pintype "bidirectional"))
      (node (ref "U6") (pin "P$18") (pinfunction "~{OUT13}_P$18") (pintype "bidirectional"))
    )
    (net (code "87") (name "/DISP5_M") (class "Default")
      (node (ref "DISP5") (pin "P$2") (pinfunction "M_P$2") (pintype "bidirectional"))
      (node (ref "U6") (pin "P$19") (pinfunction "~{OUT14}_P$19") (pintype "bidirectional"))
    )
    (net (code "88") (name "/DISP5_N") (class "Default")
      (node (ref "DISP5") (pin "P$17") (pinfunction "N_P$17") (pintype "bidirectional"))
      (node (ref "U6") (pin "P$6") (pinfunction "~{OUT1}_P$6") (pintype "bidirectional"))
    )
    (net (code "89") (name "/DISP5_P") (class "Default")
      (node (ref "DISP5") (pin "P$15") (pinfunction "P_P$15") (pintype "bidirectional"))
      (node (ref "U6") (pin "P$8") (pinfunction "~{OUT3}_P$8") (pintype "bidirectional"))
    )
    (net (code "90") (name "/DISP5_R") (class "Default")
      (node (ref "DISP5") (pin "P$14") (pinfunction "R_P$14") (pintype "bidirectional"))
      (node (ref "U6") (pin "P$9") (pinfunction "~{OUT4}_P$9") (pintype "bidirectional"))
    )
    (net (code "91") (name "/DISP5_S") (class "Default")
      (node (ref "DISP5") (pin "P$6") (pinfunction "S_P$6") (pintype "bidirectional"))
      (node (ref "U6") (pin "P$15") (pinfunction "~{OUT10}_P$15") (pintype "bidirectional"))
    )
    (net (code "92") (name "/DISP5_T") (class "Default")
      (node (ref "DISP5") (pin "P$7") (pinfunction "T_P$7") (pintype "bidirectional"))
      (node (ref "U6") (pin "P$14") (pinfunction "~{OUT9}_P$14") (pintype "bidirectional"))
    )
    (net (code "93") (name "/DISP5_U") (class "Default")
      (node (ref "DISP5") (pin "P$5") (pinfunction "U_P$5") (pintype "bidirectional"))
      (node (ref "U6") (pin "P$16") (pinfunction "~{OUT11}_P$16") (pintype "bidirectional"))
    )
    (net (code "94") (name "/DISP6_DATA") (class "Default")
      (node (ref "U6") (pin "P$22") (pinfunction "SDO_P$22") (pintype "bidirectional"))
      (node (ref "U9") (pin "P$2") (pinfunction "SDI_P$2") (pintype "bidirectional"))
    )
    (net (code "95") (name "/DISP7_DATA") (class "Default")
      (node (ref "U10") (pin "P$2") (pinfunction "SDI_P$2") (pintype "bidirectional"))
      (node (ref "U9") (pin "P$22") (pinfunction "SDO_P$22") (pintype "bidirectional"))
    )
    (net (code "96") (name "/DISP8_DATA") (class "Default")
      (node (ref "U10") (pin "P$22") (pinfunction "SDO_P$22") (pintype "bidirectional"))
      (node (ref "U14") (pin "P$2") (pinfunction "SDI_P$2") (pintype "bidirectional"))
    )
    (net (code "97") (name "/DISP9_DATA") (class "Default")
      (node (ref "U14") (pin "P$22") (pinfunction "SDO_P$22") (pintype "bidirectional"))
    )
    (net (code "98") (name "/DISPX_CLK") (class "Default")
      (node (ref "U1") (pin "44") (pinfunction "P3_44") (pintype "bidirectional"))
      (node (ref "U10") (pin "P$3") (pinfunction "CLK_P$3") (pintype "bidirectional"))
      (node (ref "U14") (pin "P$3") (pinfunction "CLK_P$3") (pintype "bidirectional"))
      (node (ref "U2") (pin "P$3") (pinfunction "CLK_P$3") (pintype "bidirectional"))
      (node (ref "U3") (pin "P$3") (pinfunction "CLK_P$3") (pintype "bidirectional"))
      (node (ref "U4") (pin "P$3") (pinfunction "CLK_P$3") (pintype "bidirectional"))
      (node (ref "U5") (pin "P$3") (pinfunction "CLK_P$3") (pintype "bidirectional"))
      (node (ref "U6") (pin "P$3") (pinfunction "CLK_P$3") (pintype "bidirectional"))
      (node (ref "U9") (pin "P$3") (pinfunction "CLK_P$3") (pintype "bidirectional"))
    )
    (net (code "99") (name "/DISPX_LAT") (class "Default")
      (node (ref "U1") (pin "1") (pinfunction "P4_1") (pintype "bidirectional"))
      (node (ref "U10") (pin "P$4") (pinfunction "LE/DM1_P$4") (pintype "bidirectional"))
      (node (ref "U14") (pin "P$4") (pinfunction "LE/DM1_P$4") (pintype "bidirectional"))
      (node (ref "U2") (pin "P$4") (pinfunction "LE/DM1_P$4") (pintype "bidirectional"))
      (node (ref "U3") (pin "P$4") (pinfunction "LE/DM1_P$4") (pintype "bidirectional"))
      (node (ref "U4") (pin "P$4") (pinfunction "LE/DM1_P$4") (pintype "bidirectional"))
      (node (ref "U5") (pin "P$4") (pinfunction "LE/DM1_P$4") (pintype "bidirectional"))
      (node (ref "U6") (pin "P$4") (pinfunction "LE/DM1_P$4") (pintype "bidirectional"))
      (node (ref "U9") (pin "P$4") (pinfunction "LE/DM1_P$4") (pintype "bidirectional"))
    )
    (net (code "100") (name "/ENCODER_A") (class "Default")
      (node (ref "C25") (pin "1") (pinfunction "1_1") (pintype "passive"))
      (node (ref "R18") (pin "2") (pinfunction "2_2") (pintype "passive"))
      (node (ref "U1") (pin "4") (pinfunction "P7_4") (pintype "bidirectional"))
    )
    (net (code "101") (name "/ENCODER_B") (class "Default")
      (node (ref "C26") (pin "1") (pinfunction "1_1") (pintype "passive"))
      (node (ref "R19") (pin "1") (pinfunction "1_1") (pintype "passive"))
      (node (ref "U1") (pin "3") (pinfunction "P6_3") (pintype "bidirectional"))
    )
    (net (code "102") (name "/LCD_SCK") (class "Default")
      (node (ref "LCD1") (pin "P$16") (pinfunction "SCK_P$16") (pintype "bidirectional"))
      (node (ref "U1") (pin "43") (pinfunction "P2_43") (pintype "bidirectional"))
    )
    (net (code "103") (name "/LCD_SI{slash}SO") (class "Default")
      (node (ref "LCD1") (pin "P$19") (pinfunction "SI/SO_P$19") (pintype "bidirectional"))
      (node (ref "U1") (pin "41") (pinfunction "P0_41") (pintype "bidirectional"))
    )
    (net (code "104") (name "/LCD_STB") (class "Default")
      (node (ref "LCD1") (pin "P$17") (pinfunction "STB_P$17") (pintype "bidirectional"))
      (node (ref "U1") (pin "42") (pinfunction "P1_42") (pintype "bidirectional"))
    )
    (net (code "105") (name "/P11") (class "Default")
      (node (ref "J2") (pin "1") (pinfunction "1_1") (pintype "bidirectional"))
      (node (ref "U1") (pin "12") (pinfunction "P11_12") (pintype "bidirectional"))
    )
    (net (code "106") (name "/P12") (class "Default")
      (node (ref "J2") (pin "2") (pinfunction "2_2") (pintype "bidirectional"))
      (node (ref "U1") (pin "13") (pinfunction "P12_13") (pintype "bidirectional"))
    )
    (net (code "107") (name "/P13") (class "Default")
      (node (ref "J2") (pin "3") (pinfunction "3_3") (pintype "bidirectional"))
      (node (ref "U1") (pin "14") (pinfunction "P13_14") (pintype "bidirectional"))
    )
    (net (code "108") (name "/P14") (class "Default")
      (node (ref "J2") (pin "4") (pinfunction "4_4") (pintype "bidirectional"))
      (node (ref "U1") (pin "15") (pinfunction "P14_15") (pintype "bidirectional"))
    )
    (net (code "109") (name "/P15") (class "Default")
      (node (ref "J2") (pin "5") (pinfunction "5_5") (pintype "bidirectional"))
      (node (ref "U1") (pin "16") (pinfunction "P15_16") (pintype "bidirectional"))
    )
    (net (code "110") (name "/P16") (class "Default")
      (node (ref "J2") (pin "6") (pinfunction "6_6") (pintype "bidirectional"))
      (node (ref "U1") (pin "19") (pinfunction "P16_19") (pintype "bidirectional"))
    )
    (net (code "111") (name "/P17") (class "Default")
      (node (ref "J2") (pin "7") (pinfunction "7_7") (pintype "bidirectional"))
      (node (ref "U1") (pin "20") (pinfunction "P17_20") (pintype "bidirectional"))
    )
    (net (code "112") (name "/P18") (class "Default")
      (node (ref "J2") (pin "8") (pinfunction "8_8") (pintype "bidirectional"))
      (node (ref "U1") (pin "21") (pinfunction "P18_21") (pintype "bidirectional"))
    )
    (net (code "113") (name "/P19") (class "Default")
      (node (ref "U1") (pin "22") (pinfunction "P19_22") (pintype "bidirectional"))
    )
    (net (code "114") (name "/P20") (class "Default")
      (node (ref "U1") (pin "23") (pinfunction "P20_23") (pintype "bidirectional"))
    )
    (net (code "115") (name "/P21") (class "Default")
      (node (ref "U1") (pin "24") (pinfunction "P21_24") (pintype "bidirectional"))
    )
    (net (code "116") (name "/P22") (class "Default")
      (node (ref "U1") (pin "25") (pinfunction "P22_25") (pintype "bidirectional"))
    )
    (net (code "117") (name "/P23") (class "Default")
      (node (ref "U1") (pin "26") (pinfunction "P23_26") (pintype "bidirectional"))
    )
    (net (code "118") (name "/P24") (class "Default")
      (node (ref "U1") (pin "31") (pinfunction "P24_31") (pintype "bidirectional"))
    )
    (net (code "119") (name "/P25") (class "Default")
      (node (ref "U1") (pin "32") (pinfunction "P25_32") (pintype "bidirectional"))
    )
    (net (code "120") (name "/P26") (class "Default")
      (node (ref "U1") (pin "33") (pinfunction "P26_33") (pintype "bidirectional"))
    )
    (net (code "121") (name "/P27") (class "Default")
      (node (ref "U1") (pin "34") (pinfunction "P27_34") (pintype "bidirectional"))
    )
    (net (code "122") (name "/RES") (class "Default")
      (node (ref "C21") (pin "1") (pinfunction "1_1") (pintype "passive"))
      (node (ref "R14") (pin "1") (pinfunction "1_1") (pintype "passive"))
      (node (ref "U1") (pin "7") (pinfunction "~{RES}_7") (pintype "bidirectional"))
    )
    (net (code "123") (name "/RX") (class "Default")
      (node (ref "U1") (pin "37") (pinfunction "P30_37") (pintype "bidirectional"))
      (node (ref "U13") (pin "10") (pinfunction "RXD_10") (pintype "bidirectional"))
    )
    (net (code "124") (name "/SCL") (class "Default")
      (node (ref "R12") (pin "1") (pinfunction "1_1") (pintype "passive"))
      (node (ref "U1") (pin "35") (pinfunction "P28_35") (pintype "bidirectional"))
      (node (ref "U11") (pin "6") (pinfunction "SCL_6") (pintype "bidirectional"))
    )
    (net (code "125") (name "/SDA") (class "Default")
      (node (ref "R13") (pin "1") (pinfunction "1_1") (pintype "passive"))
      (node (ref "U1") (pin "36") (pinfunction "P29_36") (pintype "bidirectional"))
      (node (ref "U11") (pin "5") (pinfunction "SDA_5") (pintype "bidirectional"))
    )
    (net (code "126") (name "/SHIELD") (class "Default")
      (node (ref "J1") (pin "S1") (pinfunction "SLD_S1") (pintype "power_in"))
      (node (ref "J1") (pin "S2") (pinfunction "SLD_S2") (pintype "power_in"))
      (node (ref "L1") (pin "P$1") (pinfunction "P$1_P$1") (pintype "passive"))
    )
    (net (code "127") (name "/SW_1") (class "Default")
      (node (ref "SW1") (pin "4") (pinfunction "4_4") (pintype "bidirectional"))
      (node (ref "U1") (pin "9") (pinfunction "P8_9") (pintype "bidirectional"))
    )
    (net (code "128") (name "/SW_2") (class "Default")
      (node (ref "SW2") (pin "4") (pinfunction "4_4") (pintype "bidirectional"))
      (node (ref "U1") (pin "10") (pinfunction "P9_10") (pintype "bidirectional"))
    )
    (net (code "129") (name "/SW_3") (class "Default")
      (node (ref "SW3") (pin "3") (pinfunction "3_3") (pintype "bidirectional"))
      (node (ref "U1") (pin "11") (pinfunction "P10_11") (pintype "bidirectional"))
    )
    (net (code "130") (name "/TERMINAL_A") (class "Default")
      (node (ref "EN1") (pin "A") (pinfunction "A_A") (pintype "bidirectional"))
      (node (ref "R16") (pin "1") (pinfunction "1_1") (pintype "passive"))
      (node (ref "R18") (pin "1") (pinfunction "1_1") (pintype "passive"))
    )
    (net (code "131") (name "/TERMINAL_B") (class "Default")
      (node (ref "EN1") (pin "B") (pinfunction "B_B") (pintype "bidirectional"))
      (node (ref "R17") (pin "1") (pinfunction "1_1") (pintype "passive"))
      (node (ref "R19") (pin "2") (pinfunction "2_2") (pintype "passive"))
    )
    (net (code "132") (name "/TX") (class "Default")
      (node (ref "U1") (pin "38") (pinfunction "P31_38") (pintype "bidirectional"))
      (node (ref "U13") (pin "7") (pinfunction "TXD_7") (pintype "bidirectional"))
    )
    (net (code "133") (name "/USB_~{RST}") (class "Default")
      (node (ref "C21") (pin "2") (pinfunction "2_2") (pintype "passive"))
      (node (ref "U13") (pin "8") (pinfunction "RTS#_8") (pintype "bidirectional"))
    )
    (net (code "134") (name "/VBUS_SENSE") (class "Default")
      (node (ref "R10") (pin "P$2") (pinfunction "P$2_P$2") (pintype "passive"))
      (node (ref "R11") (pin "P$1") (pinfunction "P$1_P$1") (pintype "passive"))
      (node (ref "U13") (pin "6") (pinfunction "CBUS0_6") (pintype "bidirectional"))
    )
    (net (code "135") (name "/V_USB_0") (class "Default")
      (node (ref "J1") (pin "1") (pinfunction "5V_1") (pintype "bidirectional"))
      (node (ref "R11") (pin "P$2") (pinfunction "P$2_P$2") (pintype "passive"))
      (node (ref "U12") (pin "5") (pinfunction "VB_5") (pintype "bidirectional"))
    )
    (net (code "136") (name "/X0") (class "Default")
      (node (ref "U1") (pin "29") (pinfunction "X0_29") (pintype "bidirectional"))
      (node (ref "X1") (pin "P$3") (pinfunction "X1_P$3") (pintype "bidirectional"))
    )
    (net (code "137") (name "/X1") (class "Default")
      (node (ref "U1") (pin "28") (pinfunction "X1_28") (pintype "bidirectional"))
      (node (ref "X1") (pin "P$1") (pinfunction "X0_P$1") (pintype "bidirectional"))
    )
    (net (code "138") (name "2.5V") (class "Default")
      (node (ref "C3") (pin "POS") (pinfunction "POS_POS") (pintype "bidirectional"))
      (node (ref "D1") (pin "A") (pinfunction "ANODE_A") (pintype "bidirectional"))
      (node (ref "D10") (pin "A") (pinfunction "ANODE_A") (pintype "bidirectional"))
      (node (ref "D11") (pin "A") (pinfunction "ANODE_A") (pintype "bidirectional"))
      (node (ref "D12") (pin "A") (pinfunction "ANODE_A") (pintype "bidirectional"))
      (node (ref "D13") (pin "A") (pinfunction "ANODE_A") (pintype "bidirectional"))
      (node (ref "D14") (pin "A") (pinfunction "ANODE_A") (pintype "bidirectional"))
      (node (ref "D15") (pin "A") (pinfunction "ANODE_A") (pintype "bidirectional"))
      (node (ref "D16") (pin "A") (pinfunction "ANODE_A") (pintype "bidirectional"))
      (node (ref "D17") (pin "A") (pinfunction "ANODE_A") (pintype "bidirectional"))
      (node (ref "D18") (pin "A") (pinfunction "ANODE_A") (pintype "bidirectional"))
      (node (ref "D19") (pin "A") (pinfunction "ANODE_A") (pintype "bidirectional"))
      (node (ref "D2") (pin "A") (pinfunction "ANODE_A") (pintype "bidirectional"))
      (node (ref "D20") (pin "A") (pinfunction "ANODE_A") (pintype "bidirectional"))
      (node (ref "D21") (pin "A") (pinfunction "ANODE_A") (pintype "bidirectional"))
      (node (ref "D22") (pin "A") (pinfunction "ANODE_A") (pintype "bidirectional"))
      (node (ref "D23") (pin "A") (pinfunction "ANODE_A") (pintype "bidirectional"))
      (node (ref "D24") (pin "A") (pinfunction "ANODE_A") (pintype "bidirectional"))
      (node (ref "D25") (pin "A") (pinfunction "ANODE_A") (pintype "bidirectional"))
      (node (ref "D26") (pin "A") (pinfunction "ANODE_A") (pintype "bidirectional"))
      (node (ref "D27") (pin "A") (pinfunction "ANODE_A") (pintype "bidirectional"))
      (node (ref "D3") (pin "A") (pinfunction "ANODE_A") (pintype "bidirectional"))
      (node (ref "D4") (pin "A") (pinfunction "ANODE_A") (pintype "bidirectional"))
      (node (ref "D5") (pin "A") (pinfunction "ANODE_A") (pintype "bidirectional"))
      (node (ref "D6") (pin "A") (pinfunction "ANODE_A") (pintype "bidirectional"))
      (node (ref "D7") (pin "A") (pinfunction "ANODE_A") (pintype "bidirectional"))
      (node (ref "D8") (pin "A") (pinfunction "ANODE_A") (pintype "bidirectional"))
      (node (ref "D9") (pin "A") (pinfunction "ANODE_A") (pintype "bidirectional"))
      (node (ref "DISP1") (pin "P$11") (pinfunction "COM_P$11") (pintype "bidirectional"))
      (node (ref "DISP2") (pin "P$11") (pinfunction "COM_P$11") (pintype "bidirectional"))
      (node (ref "DISP3") (pin "P$11") (pinfunction "COM_P$11") (pintype "bidirectional"))
      (node (ref "DISP4") (pin "P$11") (pinfunction "COM_P$11") (pintype "bidirectional"))
      (node (ref "DISP5") (pin "P$11") (pinfunction "COM_P$11") (pintype "bidirectional"))
      (node (ref "SW1") (pin "ANODE_1") (pinfunction "ANODE_1_ANODE_1") (pintype "bidirectional"))
      (node (ref "SW1") (pin "ANODE_2") (pinfunction "ANODE_2_ANODE_2") (pintype "bidirectional"))
      (node (ref "SW2") (pin "ANODE_1") (pinfunction "ANODE_1_ANODE_1") (pintype "bidirectional"))
      (node (ref "SW2") (pin "ANODE_2") (pinfunction "ANODE_2_ANODE_2") (pintype "bidirectional"))
      (node (ref "SW3") (pin "ANODE_1") (pinfunction "ANODE_1_ANODE_1") (pintype "bidirectional"))
      (node (ref "SW3") (pin "ANODE_2") (pinfunction "ANODE_2_ANODE_2") (pintype "bidirectional"))
      (node (ref "U7") (pin "3") (pinfunction "OUT_3") (pintype "bidirectional"))
    )
    (net (code "139") (name "3.3V") (class "Default")
      (node (ref "C1") (pin "1") (pinfunction "1_1") (pintype "passive"))
      (node (ref "C10") (pin "1") (pinfunction "1_1") (pintype "passive"))
      (node (ref "C11") (pin "1") (pinfunction "1_1") (pintype "passive"))
      (node (ref "C15") (pin "P$1") (pinfunction "P$1_P$1") (pintype "passive"))
      (node (ref "C16") (pin "P$1") (pinfunction "P$1_P$1") (pintype "passive"))
      (node (ref "C17") (pin "2") (pinfunction "2_2") (pintype "passive"))
      (node (ref "C18") (pin "2") (pinfunction "2_2") (pintype "passive"))
      (node (ref "C19") (pin "2") (pinfunction "2_2") (pintype "passive"))
      (node (ref "C20") (pin "2") (pinfunction "2_2") (pintype "passive"))
      (node (ref "C22") (pin "2") (pinfunction "2_2") (pintype "passive"))
      (node (ref "C23") (pin "2") (pinfunction "2_2") (pintype "passive"))
      (node (ref "C24") (pin "1") (pinfunction "1_1") (pintype "passive"))
      (node (ref "C5") (pin "POS") (pinfunction "POS_POS") (pintype "bidirectional"))
      (node (ref "C6") (pin "1") (pinfunction "1_1") (pintype "passive"))
      (node (ref "C7") (pin "1") (pinfunction "1_1") (pintype "passive"))
      (node (ref "C8") (pin "1") (pinfunction "1_1") (pintype "passive"))
      (node (ref "C9") (pin "1") (pinfunction "1_1") (pintype "passive"))
      (node (ref "EN1") (pin "5") (pinfunction "5_5") (pintype "bidirectional"))
      (node (ref "R12") (pin "2") (pinfunction "2_2") (pintype "passive"))
      (node (ref "R13") (pin "2") (pinfunction "2_2") (pintype "passive"))
      (node (ref "R14") (pin "2") (pinfunction "2_2") (pintype "passive"))
      (node (ref "R16") (pin "2") (pinfunction "2_2") (pintype "passive"))
      (node (ref "R17") (pin "2") (pinfunction "2_2") (pintype "passive"))
      (node (ref "R20") (pin "1") (pinfunction "1_1") (pintype "passive"))
      (node (ref "R21") (pin "1") (pinfunction "1_1") (pintype "passive"))
      (node (ref "R22") (pin "1") (pinfunction "1_1") (pintype "passive"))
      (node (ref "U1") (pin "18") (pinfunction "VDD_18") (pintype "bidirectional"))
      (node (ref "U1") (pin "30") (pinfunction "VDD_30") (pintype "bidirectional"))
      (node (ref "U1") (pin "40") (pinfunction "VDD_40") (pintype "bidirectional"))
      (node (ref "U1") (pin "8") (pinfunction "VDD_8") (pintype "bidirectional"))
      (node (ref "U10") (pin "P$24") (pinfunction "VDD_P$24") (pintype "bidirectional"))
      (node (ref "U11") (pin "8") (pinfunction "VCC_8") (pintype "bidirectional"))
      (node (ref "U13") (pin "4") (pinfunction "VCC_4") (pintype "bidirectional"))
      (node (ref "U14") (pin "P$24") (pinfunction "VDD_P$24") (pintype "bidirectional"))
      (node (ref "U2") (pin "P$24") (pinfunction "VDD_P$24") (pintype "bidirectional"))
      (node (ref "U3") (pin "P$24") (pinfunction "VDD_P$24") (pintype "bidirectional"))
      (node (ref "U4") (pin "P$24") (pinfunction "VDD_P$24") (pintype "bidirectional"))
      (node (ref "U5") (pin "P$24") (pinfunction "VDD_P$24") (pintype "bidirectional"))
      (node (ref "U6") (pin "P$24") (pinfunction "VDD_P$24") (pintype "bidirectional"))
      (node (ref "U8") (pin "3") (pinfunction "OUT_3") (pintype "bidirectional"))
      (node (ref "U9") (pin "P$24") (pinfunction "VDD_P$24") (pintype "bidirectional"))
    )
    (net (code "140") (name "GND") (class "Default")
      (node (ref "C1") (pin "2") (pinfunction "2_2") (pintype "passive"))
      (node (ref "C10") (pin "2") (pinfunction "2_2") (pintype "passive"))
      (node (ref "C11") (pin "2") (pinfunction "2_2") (pintype "passive"))
      (node (ref "C12") (pin "P$2") (pinfunction "P$2_P$2") (pintype "passive"))
      (node (ref "C13") (pin "P$2") (pinfunction "P$2_P$2") (pintype "passive"))
      (node (ref "C14") (pin "P$2") (pinfunction "P$2_P$2") (pintype "passive"))
      (node (ref "C15") (pin "P$2") (pinfunction "P$2_P$2") (pintype "passive"))
      (node (ref "C16") (pin "P$2") (pinfunction "P$2_P$2") (pintype "passive"))
      (node (ref "C17") (pin "1") (pinfunction "1_1") (pintype "passive"))
      (node (ref "C18") (pin "1") (pinfunction "1_1") (pintype "passive"))
      (node (ref "C19") (pin "1") (pinfunction "1_1") (pintype "passive"))
      (node (ref "C2") (pin "NEG") (pinfunction "NEG_NEG") (pintype "bidirectional"))
      (node (ref "C20") (pin "1") (pinfunction "1_1") (pintype "passive"))
      (node (ref "C22") (pin "1") (pinfunction "1_1") (pintype "passive"))
      (node (ref "C23") (pin "1") (pinfunction "1_1") (pintype "passive"))
      (node (ref "C24") (pin "2") (pinfunction "2_2") (pintype "passive"))
      (node (ref "C25") (pin "2") (pinfunction "2_2") (pintype "passive"))
      (node (ref "C26") (pin "2") (pinfunction "2_2") (pintype "passive"))
      (node (ref "C3") (pin "NEG") (pinfunction "NEG_NEG") (pintype "bidirectional"))
      (node (ref "C4") (pin "NEG") (pinfunction "NEG_NEG") (pintype "bidirectional"))
      (node (ref "C5") (pin "NEG") (pinfunction "NEG_NEG") (pintype "bidirectional"))
      (node (ref "C6") (pin "2") (pinfunction "2_2") (pintype "passive"))
      (node (ref "C7") (pin "2") (pinfunction "2_2") (pintype "passive"))
      (node (ref "C8") (pin "2") (pinfunction "2_2") (pintype "passive"))
      (node (ref "C9") (pin "2") (pinfunction "2_2") (pintype "passive"))
      (node (ref "EN1") (pin "C") (pinfunction "C_C") (pintype "bidirectional"))
      (node (ref "GND") (pin "P$1") (pinfunction "P$1_P$1") (pintype "bidirectional"))
      (node (ref "J1") (pin "4") (pinfunction "GND_4") (pintype "bidirectional"))
      (node (ref "L1") (pin "P$2") (pinfunction "P$2_P$2") (pintype "passive"))
      (node (ref "LCD1") (pin "P$18") (pinfunction "GND2_P$18") (pintype "bidirectional"))
      (node (ref "R1") (pin "1") (pinfunction "1_1") (pintype "passive"))
      (node (ref "R10") (pin "P$1") (pinfunction "P$1_P$1") (pintype "passive"))
      (node (ref "R15") (pin "1") (pinfunction "1_1") (pintype "passive"))
      (node (ref "R2") (pin "1") (pinfunction "1_1") (pintype "passive"))
      (node (ref "R3") (pin "1") (pinfunction "1_1") (pintype "passive"))
      (node (ref "R4") (pin "1") (pinfunction "1_1") (pintype "passive"))
      (node (ref "R5") (pin "1") (pinfunction "1_1") (pintype "passive"))
      (node (ref "R6") (pin "1") (pinfunction "1_1") (pintype "passive"))
      (node (ref "R7") (pin "1") (pinfunction "1_1") (pintype "passive"))
      (node (ref "SW1") (pin "1") (pinfunction "1_1") (pintype "bidirectional"))
      (node (ref "SW2") (pin "1") (pinfunction "1_1") (pintype "bidirectional"))
      (node (ref "SW3") (pin "1A") (pinfunction "1A_1A") (pintype "bidirectional"))
      (node (ref "U1") (pin "17") (pinfunction "VSS_17") (pintype "bidirectional"))
      (node (ref "U1") (pin "27") (pinfunction "VSS_27") (pintype "bidirectional"))
      (node (ref "U1") (pin "39") (pinfunction "VSS_39") (pintype "bidirectional"))
      (node (ref "U1") (pin "5") (pinfunction "VSS_5") (pintype "bidirectional"))
      (node (ref "U1") (pin "6") (pinfunction "~{BOE}_6") (pintype "bidirectional"))
      (node (ref "U10") (pin "P$1") (pinfunction "VSS/GND_P$1") (pintype "bidirectional"))
      (node (ref "U10") (pin "P$21") (pinfunction "~{OE/DM2}_P$21") (pintype "bidirectional"))
      (node (ref "U10") (pin "PAD") (pinfunction "VSS/GND_PAD") (pintype "bidirectional"))
      (node (ref "U11") (pin "1") (pinfunction "A0_1") (pintype "bidirectional"))
      (node (ref "U11") (pin "2") (pinfunction "A1_2") (pintype "bidirectional"))
      (node (ref "U11") (pin "3") (pinfunction "A2_3") (pintype "bidirectional"))
      (node (ref "U11") (pin "4") (pinfunction "GND_4") (pintype "bidirectional"))
      (node (ref "U11") (pin "7") (pinfunction "WP_7") (pintype "bidirectional"))
      (node (ref "U12") (pin "2") (pinfunction "GND_2") (pintype "bidirectional"))
      (node (ref "U13") (pin "5") (pinfunction "GND_5") (pintype "bidirectional"))
      (node (ref "U13") (pin "P$1") (pinfunction "GND_P$1") (pintype "bidirectional"))
      (node (ref "U14") (pin "P$1") (pinfunction "VSS/GND_P$1") (pintype "bidirectional"))
      (node (ref "U14") (pin "P$21") (pinfunction "~{OE/DM2}_P$21") (pintype "bidirectional"))
      (node (ref "U14") (pin "PAD") (pinfunction "VSS/GND_PAD") (pintype "bidirectional"))
      (node (ref "U2") (pin "P$1") (pinfunction "VSS/GND_P$1") (pintype "bidirectional"))
      (node (ref "U2") (pin "P$21") (pinfunction "~{OE/DM2}_P$21") (pintype "bidirectional"))
      (node (ref "U2") (pin "PAD") (pinfunction "VSS/GND_PAD") (pintype "bidirectional"))
      (node (ref "U3") (pin "P$1") (pinfunction "VSS/GND_P$1") (pintype "bidirectional"))
      (node (ref "U3") (pin "P$21") (pinfunction "~{OE/DM2}_P$21") (pintype "bidirectional"))
      (node (ref "U3") (pin "PAD") (pinfunction "VSS/GND_PAD") (pintype "bidirectional"))
      (node (ref "U4") (pin "P$1") (pinfunction "VSS/GND_P$1") (pintype "bidirectional"))
      (node (ref "U4") (pin "P$21") (pinfunction "~{OE/DM2}_P$21") (pintype "bidirectional"))
      (node (ref "U4") (pin "PAD") (pinfunction "VSS/GND_PAD") (pintype "bidirectional"))
      (node (ref "U5") (pin "P$1") (pinfunction "VSS/GND_P$1") (pintype "bidirectional"))
      (node (ref "U5") (pin "P$21") (pinfunction "~{OE/DM2}_P$21") (pintype "bidirectional"))
      (node (ref "U5") (pin "PAD") (pinfunction "VSS/GND_PAD") (pintype "bidirectional"))
      (node (ref "U6") (pin "P$1") (pinfunction "VSS/GND_P$1") (pintype "bidirectional"))
      (node (ref "U6") (pin "P$21") (pinfunction "~{OE/DM2}_P$21") (pintype "bidirectional"))
      (node (ref "U6") (pin "PAD") (pinfunction "VSS/GND_PAD") (pintype "bidirectional"))
      (node (ref "U7") (pin "1") (pinfunction "GND_1") (pintype "bidirectional"))
      (node (ref "U8") (pin "1") (pinfunction "GND_1") (pintype "bidirectional"))
      (node (ref "U9") (pin "P$1") (pinfunction "VSS/GND_P$1") (pintype "bidirectional"))
      (node (ref "U9") (pin "P$21") (pinfunction "~{OE/DM2}_P$21") (pintype "bidirectional"))
      (node (ref "U9") (pin "PAD") (pinfunction "VSS/GND_PAD") (pintype "bidirectional"))
      (node (ref "X1") (pin "P$2") (pinfunction "GND_P$2") (pintype "bidirectional"))
      (node (ref "X1") (pin "P$4") (pinfunction "GND_P$4") (pintype "bidirectional"))
    )
    (net (code "141") (name "Net-(D1-CATHODE)") (class "Default")
      (node (ref "D1") (pin "C") (pinfunction "CATHODE_C") (pintype "bidirectional"))
      (node (ref "U9") (pin "P$20") (pinfunction "~{OUT15}_P$20") (pintype "bidirectional"))
    )
    (net (code "142") (name "Net-(D2-CATHODE)") (class "Default")
      (node (ref "D2") (pin "C") (pinfunction "CATHODE_C") (pintype "bidirectional"))
      (node (ref "U9") (pin "P$19") (pinfunction "~{OUT14}_P$19") (pintype "bidirectional"))
    )
    (net (code "143") (name "Net-(D3-CATHODE)") (class "Default")
      (node (ref "D3") (pin "C") (pinfunction "CATHODE_C") (pintype "bidirectional"))
      (node (ref "U9") (pin "P$18") (pinfunction "~{OUT13}_P$18") (pintype "bidirectional"))
    )
    (net (code "144") (name "Net-(D4-CATHODE)") (class "Default")
      (node (ref "D4") (pin "C") (pinfunction "CATHODE_C") (pintype "bidirectional"))
      (node (ref "U9") (pin "P$17") (pinfunction "~{OUT12}_P$17") (pintype "bidirectional"))
    )
    (net (code "145") (name "Net-(D5-CATHODE)") (class "Default")
      (node (ref "D5") (pin "C") (pinfunction "CATHODE_C") (pintype "bidirectional"))
      (node (ref "U9") (pin "P$16") (pinfunction "~{OUT11}_P$16") (pintype "bidirectional"))
    )
    (net (code "146") (name "Net-(D6-CATHODE)") (class "Default")
      (node (ref "D6") (pin "C") (pinfunction "CATHODE_C") (pintype "bidirectional"))
      (node (ref "U9") (pin "P$15") (pinfunction "~{OUT10}_P$15") (pintype "bidirectional"))
    )
    (net (code "147") (name "Net-(D7-CATHODE)") (class "Default")
      (node (ref "D7") (pin "C") (pinfunction "CATHODE_C") (pintype "bidirectional"))
      (node (ref "U9") (pin "P$14") (pinfunction "~{OUT9}_P$14") (pintype "bidirectional"))
    )
    (net (code "148") (name "Net-(D8-CATHODE)") (class "Default")
      (node (ref "D8") (pin "C") (pinfunction "CATHODE_C") (pintype "bidirectional"))
      (node (ref "U9") (pin "P$13") (pinfunction "~{OUT8}_P$13") (pintype "bidirectional"))
    )
    (net (code "149") (name "Net-(D9-CATHODE)") (class "Default")
      (node (ref "D9") (pin "C") (pinfunction "CATHODE_C") (pintype "bidirectional"))
      (node (ref "U9") (pin "P$12") (pinfunction "~{OUT7}_P$12") (pintype "bidirectional"))
    )
    (net (code "150") (name "Net-(D10-CATHODE)") (class "Default")
      (node (ref "D10") (pin "C") (pinfunction "CATHODE_C") (pintype "bidirectional"))
      (node (ref "U9") (pin "P$11") (pinfunction "~{OUT6}_P$11") (pintype "bidirectional"))
    )
    (net (code "151") (name "Net-(D11-CATHODE)") (class "Default")
      (node (ref "D11") (pin "C") (pinfunction "CATHODE_C") (pintype "bidirectional"))
      (node (ref "U9") (pin "P$10") (pinfunction "~{OUT5}_P$10") (pintype "bidirectional"))
    )
    (net (code "152") (name "Net-(D12-CATHODE)") (class "Default")
      (node (ref "D12") (pin "C") (pinfunction "CATHODE_C") (pintype "bidirectional"))
      (node (ref "U9") (pin "P$9") (pinfunction "~{OUT4}_P$9") (pintype "bidirectional"))
    )
    (net (code "153") (name "Net-(D13-CATHODE)") (class "Default")
      (node (ref "D13") (pin "C") (pinfunction "CATHODE_C") (pintype "bidirectional"))
      (node (ref "U9") (pin "P$8") (pinfunction "~{OUT3}_P$8") (pintype "bidirectional"))
    )
    (net (code "154") (name "Net-(D14-CATHODE)") (class "Default")
      (node (ref "D14") (pin "C") (pinfunction "CATHODE_C") (pintype "bidirectional"))
      (node (ref "U9") (pin "P$7") (pinfunction "~{OUT2}_P$7") (pintype "bidirectional"))
    )
    (net (code "155") (name "Net-(D15-CATHODE)") (class "Default")
      (node (ref "D15") (pin "C") (pinfunction "CATHODE_C") (pintype "bidirectional"))
      (node (ref "U9") (pin "P$6") (pinfunction "~{OUT1}_P$6") (pintype "bidirectional"))
    )
    (net (code "156") (name "Net-(D16-CATHODE)") (class "Default")
      (node (ref "D16") (pin "C") (pinfunction "CATHODE_C") (pintype "bidirectional"))
      (node (ref "U9") (pin "P$5") (pinfunction "~{OUT0}_P$5") (pintype "bidirectional"))
    )
    (net (code "157") (name "Net-(D17-CATHODE)") (class "Default")
      (node (ref "D17") (pin "C") (pinfunction "CATHODE_C") (pintype "bidirectional"))
      (node (ref "U10") (pin "P$20") (pinfunction "~{OUT15}_P$20") (pintype "bidirectional"))
    )
    (net (code "158") (name "Net-(D18-CATHODE)") (class "Default")
      (node (ref "D18") (pin "C") (pinfunction "CATHODE_C") (pintype "bidirectional"))
      (node (ref "U10") (pin "P$19") (pinfunction "~{OUT14}_P$19") (pintype "bidirectional"))
    )
    (net (code "159") (name "Net-(D19-CATHODE)") (class "Default")
      (node (ref "D19") (pin "C") (pinfunction "CATHODE_C") (pintype "bidirectional"))
      (node (ref "U10") (pin "P$18") (pinfunction "~{OUT13}_P$18") (pintype "bidirectional"))
    )
    (net (code "160") (name "Net-(D20-CATHODE)") (class "Default")
      (node (ref "D20") (pin "C") (pinfunction "CATHODE_C") (pintype "bidirectional"))
      (node (ref "U10") (pin "P$17") (pinfunction "~{OUT12}_P$17") (pintype "bidirectional"))
    )
    (net (code "161") (name "Net-(D21-CATHODE)") (class "Default")
      (node (ref "D21") (pin "C") (pinfunction "CATHODE_C") (pintype "bidirectional"))
      (node (ref "U10") (pin "P$16") (pinfunction "~{OUT11}_P$16") (pintype "bidirectional"))
    )
    (net (code "162") (name "Net-(D22-CATHODE)") (class "Default")
      (node (ref "D22") (pin "C") (pinfunction "CATHODE_C") (pintype "bidirectional"))
      (node (ref "U10") (pin "P$15") (pinfunction "~{OUT10}_P$15") (pintype "bidirectional"))
    )
    (net (code "163") (name "Net-(D23-CATHODE)") (class "Default")
      (node (ref "D23") (pin "C") (pinfunction "CATHODE_C") (pintype "bidirectional"))
      (node (ref "U10") (pin "P$14") (pinfunction "~{OUT9}_P$14") (pintype "bidirectional"))
    )
    (net (code "164") (name "Net-(D24-CATHODE)") (class "Default")
      (node (ref "D24") (pin "C") (pinfunction "CATHODE_C") (pintype "bidirectional"))
      (node (ref "U10") (pin "P$13") (pinfunction "~{OUT8}_P$13") (pintype "bidirectional"))
    )
    (net (code "165") (name "Net-(D25-CATHODE)") (class "Default")
      (node (ref "D25") (pin "C") (pinfunction "CATHODE_C") (pintype "bidirectional"))
      (node (ref "U10") (pin "P$12") (pinfunction "~{OUT7}_P$12") (pintype "bidirectional"))
    )
    (net (code "166") (name "Net-(D26-CATHODE)") (class "Default")
      (node (ref "D26") (pin "C") (pinfunction "CATHODE_C") (pintype "bidirectional"))
      (node (ref "U10") (pin "P$11") (pinfunction "~{OUT6}_P$11") (pintype "bidirectional"))
    )
    (net (code "167") (name "Net-(D27-CATHODE)") (class "Default")
      (node (ref "D27") (pin "C") (pinfunction "CATHODE_C") (pintype "bidirectional"))
      (node (ref "U10") (pin "P$10") (pinfunction "~{OUT5}_P$10") (pintype "bidirectional"))
    )
    (net (code "168") (name "Net-(R20-Pad2)") (class "Default")
      (node (ref "R20") (pin "2") (pinfunction "2_2") (pintype "passive"))
      (node (ref "SW1") (pin "3") (pinfunction "3_3") (pintype "bidirectional"))
    )
    (net (code "169") (name "Net-(R21-Pad2)") (class "Default")
      (node (ref "R21") (pin "2") (pinfunction "2_2") (pintype "passive"))
      (node (ref "SW2") (pin "3") (pinfunction "3_3") (pintype "bidirectional"))
    )
    (net (code "170") (name "Net-(R22-Pad2)") (class "Default")
      (node (ref "R22") (pin "2") (pinfunction "2_2") (pintype "passive"))
      (node (ref "SW3") (pin "2") (pinfunction "2_2") (pintype "bidirectional"))
    )
    (net (code "171") (name "Net-(U2-R-EXT)") (class "Default")
      (node (ref "R1") (pin "2") (pinfunction "2_2") (pintype "passive"))
      (node (ref "U2") (pin "P$23") (pinfunction "R-EXT_P$23") (pintype "bidirectional"))
    )
    (net (code "172") (name "Net-(U3-R-EXT)") (class "Default")
      (node (ref "R2") (pin "2") (pinfunction "2_2") (pintype "passive"))
      (node (ref "U3") (pin "P$23") (pinfunction "R-EXT_P$23") (pintype "bidirectional"))
    )
    (net (code "173") (name "Net-(U4-R-EXT)") (class "Default")
      (node (ref "R3") (pin "2") (pinfunction "2_2") (pintype "passive"))
      (node (ref "U4") (pin "P$23") (pinfunction "R-EXT_P$23") (pintype "bidirectional"))
    )
    (net (code "174") (name "Net-(U5-R-EXT)") (class "Default")
      (node (ref "R4") (pin "2") (pinfunction "2_2") (pintype "passive"))
      (node (ref "U5") (pin "P$23") (pinfunction "R-EXT_P$23") (pintype "bidirectional"))
    )
    (net (code "175") (name "Net-(U6-R-EXT)") (class "Default")
      (node (ref "R5") (pin "2") (pinfunction "2_2") (pintype "passive"))
      (node (ref "U6") (pin "P$23") (pinfunction "R-EXT_P$23") (pintype "bidirectional"))
    )
    (net (code "176") (name "Net-(U9-R-EXT)") (class "Default")
      (node (ref "R6") (pin "2") (pinfunction "2_2") (pintype "passive"))
      (node (ref "U9") (pin "P$23") (pinfunction "R-EXT_P$23") (pintype "bidirectional"))
    )
    (net (code "177") (name "Net-(U10-R-EXT)") (class "Default")
      (node (ref "R7") (pin "2") (pinfunction "2_2") (pintype "passive"))
      (node (ref "U10") (pin "P$23") (pinfunction "R-EXT_P$23") (pintype "bidirectional"))
    )
    (net (code "178") (name "Net-(U12-I{slash}O1B)") (class "Default")
      (node (ref "C13") (pin "P$1") (pinfunction "P$1_P$1") (pintype "passive"))
      (node (ref "R9") (pin "P$1") (pinfunction "P$1_P$1") (pintype "passive"))
      (node (ref "U12") (pin "3") (pinfunction "I/O1B_3") (pintype "bidirectional"))
    )
    (net (code "179") (name "Net-(U12-I{slash}O2B)") (class "Default")
      (node (ref "C12") (pin "P$1") (pinfunction "P$1_P$1") (pintype "passive"))
      (node (ref "R8") (pin "P$1") (pinfunction "P$1_P$1") (pintype "passive"))
      (node (ref "U12") (pin "4") (pinfunction "I/O2B_4") (pintype "bidirectional"))
    )
    (net (code "180") (name "Net-(U13-USBDM)") (class "Default")
      (node (ref "R8") (pin "P$2") (pinfunction "P$2_P$2") (pintype "passive"))
      (node (ref "U13") (pin "1") (pinfunction "USBDM_1") (pintype "bidirectional"))
    )
    (net (code "181") (name "Net-(U13-USBDP)") (class "Default")
      (node (ref "R9") (pin "P$2") (pinfunction "P$2_P$2") (pintype "passive"))
      (node (ref "U13") (pin "12") (pinfunction "USBDP_12") (pintype "bidirectional"))
    )
    (net (code "182") (name "Net-(U14-R-EXT)") (class "Default")
      (node (ref "R15") (pin "2") (pinfunction "2_2") (pintype "passive"))
      (node (ref "U14") (pin "P$23") (pinfunction "R-EXT_P$23") (pintype "bidirectional"))
    )
    (net (code "183") (name "Net-(U14-~{OUT0})") (class "Default")
      (node (ref "EN1") (pin "1") (pinfunction "1_1") (pintype "bidirectional"))
      (node (ref "U14") (pin "P$5") (pinfunction "~{OUT0}_P$5") (pintype "bidirectional"))
    )
    (net (code "184") (name "Net-(U14-~{OUT1})") (class "Default")
      (node (ref "EN1") (pin "2") (pinfunction "2_2") (pintype "bidirectional"))
      (node (ref "U14") (pin "P$6") (pinfunction "~{OUT1}_P$6") (pintype "bidirectional"))
    )
    (net (code "185") (name "Net-(U14-~{OUT2})") (class "Default")
      (node (ref "EN1") (pin "4") (pinfunction "4_4") (pintype "bidirectional"))
      (node (ref "U14") (pin "P$7") (pinfunction "~{OUT2}_P$7") (pintype "bidirectional"))
    )
    (net (code "186") (name "Net-(U14-~{OUT3})") (class "Default")
      (node (ref "SW1") (pin "CATHODE_1") (pinfunction "CATHODE_1_CATHODE_1") (pintype "bidirectional"))
      (node (ref "U14") (pin "P$8") (pinfunction "~{OUT3}_P$8") (pintype "bidirectional"))
    )
    (net (code "187") (name "Net-(U14-~{OUT4})") (class "Default")
      (node (ref "SW1") (pin "CATHODE_2") (pinfunction "CATHODE_2_CATHODE_2") (pintype "bidirectional"))
      (node (ref "U14") (pin "P$9") (pinfunction "~{OUT4}_P$9") (pintype "bidirectional"))
    )
    (net (code "188") (name "Net-(U14-~{OUT5})") (class "Default")
      (node (ref "SW2") (pin "CATHODE_1") (pinfunction "CATHODE_1_CATHODE_1") (pintype "bidirectional"))
      (node (ref "U14") (pin "P$10") (pinfunction "~{OUT5}_P$10") (pintype "bidirectional"))
    )
    (net (code "189") (name "Net-(U14-~{OUT6})") (class "Default")
      (node (ref "SW2") (pin "CATHODE_2") (pinfunction "CATHODE_2_CATHODE_2") (pintype "bidirectional"))
      (node (ref "U14") (pin "P$11") (pinfunction "~{OUT6}_P$11") (pintype "bidirectional"))
    )
    (net (code "190") (name "Net-(U14-~{OUT7})") (class "Default")
      (node (ref "SW3") (pin "CATHODE_1") (pinfunction "CATHODE_1_CATHODE_1") (pintype "bidirectional"))
      (node (ref "U14") (pin "P$12") (pinfunction "~{OUT7}_P$12") (pintype "bidirectional"))
    )
    (net (code "191") (name "Net-(U14-~{OUT8})") (class "Default")
      (node (ref "SW3") (pin "CATHODE_2") (pinfunction "CATHODE_2_CATHODE_2") (pintype "bidirectional"))
      (node (ref "U14") (pin "P$13") (pinfunction "~{OUT8}_P$13") (pintype "bidirectional"))
    )
    (net (code "192") (name "VIN") (class "Default")
      (node (ref "5V") (pin "P$1") (pinfunction "P$1_P$1") (pintype "bidirectional"))
      (node (ref "C2") (pin "POS") (pinfunction "POS_POS") (pintype "bidirectional"))
      (node (ref "C4") (pin "POS") (pinfunction "POS_POS") (pintype "bidirectional"))
      (node (ref "LCD1") (pin "P$20") (pinfunction "VCC2_P$20") (pintype "bidirectional"))
      (node (ref "U7") (pin "2") (pinfunction "IN_2") (pintype "bidirectional"))
      (node (ref "U8") (pin "2") (pinfunction "IN_2") (pintype "bidirectional"))
    )
    (net (code "193") (name "unconnected-(EN1-Pad3)") (class "Default")
      (node (ref "EN1") (pin "3") (pinfunction "3_3") (pintype "bidirectional"))
    )
    (net (code "194") (name "unconnected-(LCD1-D0-PadP$7)") (class "Default")
      (node (ref "LCD1") (pin "P$7") (pinfunction "D0_P$7") (pintype "bidirectional"))
    )
    (net (code "195") (name "unconnected-(LCD1-D1-PadP$8)") (class "Default")
      (node (ref "LCD1") (pin "P$8") (pinfunction "D1_P$8") (pintype "bidirectional"))
    )
    (net (code "196") (name "unconnected-(LCD1-D2-PadP$9)") (class "Default")
      (node (ref "LCD1") (pin "P$9") (pinfunction "D2_P$9") (pintype "bidirectional"))
    )
    (net (code "197") (name "unconnected-(LCD1-D3-PadP$10)") (class "Default")
      (node (ref "LCD1") (pin "P$10") (pinfunction "D3_P$10") (pintype "bidirectional"))
    )
    (net (code "198") (name "unconnected-(LCD1-D4-PadP$11)") (class "Default")
      (node (ref "LCD1") (pin "P$11") (pinfunction "D4_P$11") (pintype "bidirectional"))
    )
    (net (code "199") (name "unconnected-(LCD1-D5-PadP$12)") (class "Default")
      (node (ref "LCD1") (pin "P$12") (pinfunction "D5_P$12") (pintype "bidirectional"))
    )
    (net (code "200") (name "unconnected-(LCD1-D6-PadP$13)") (class "Default")
      (node (ref "LCD1") (pin "P$13") (pinfunction "D6_P$13") (pintype "bidirectional"))
    )
    (net (code "201") (name "unconnected-(LCD1-D7-PadP$14)") (class "Default")
      (node (ref "LCD1") (pin "P$14") (pinfunction "D7_P$14") (pintype "bidirectional"))
    )
    (net (code "202") (name "unconnected-(LCD1-E-PadP$6)") (class "Default")
      (node (ref "LCD1") (pin "P$6") (pinfunction "E_P$6") (pintype "bidirectional"))
    )
    (net (code "203") (name "unconnected-(LCD1-GND1-PadP$1)") (class "Default")
      (node (ref "LCD1") (pin "P$1") (pinfunction "GND1_P$1") (pintype "bidirectional"))
    )
    (net (code "204") (name "unconnected-(LCD1-RS-PadP$4)") (class "Default")
      (node (ref "LCD1") (pin "P$4") (pinfunction "RS_P$4") (pintype "bidirectional"))
    )
    (net (code "205") (name "unconnected-(LCD1-R{slash}W-PadP$5)") (class "Default")
      (node (ref "LCD1") (pin "P$5") (pinfunction "R/W_P$5") (pintype "bidirectional"))
    )
    (net (code "206") (name "unconnected-(LCD1-VCC1-PadP$2)") (class "Default")
      (node (ref "LCD1") (pin "P$2") (pinfunction "VCC1_P$2") (pintype "bidirectional"))
    )
    (net (code "207") (name "unconnected-(SW1-Pad2)") (class "Default")
      (node (ref "SW1") (pin "2") (pinfunction "2_2") (pintype "bidirectional"))
    )
    (net (code "208") (name "unconnected-(SW2-Pad2)") (class "Default")
      (node (ref "SW2") (pin "2") (pinfunction "2_2") (pintype "bidirectional"))
    )
    (net (code "209") (name "unconnected-(SW3-Pad1B)") (class "Default")
      (node (ref "SW3") (pin "1B") (pinfunction "1B_1B") (pintype "bidirectional"))
    )
    (net (code "210") (name "unconnected-(U13-CTS#-Pad11)") (class "Default")
      (node (ref "U13") (pin "11") (pinfunction "CTS#_11") (pintype "bidirectional"))
    )
    (net (code "211") (name "unconnected-(U14-~{OUT9}-PadP$14)") (class "Default")
      (node (ref "U14") (pin "P$14") (pinfunction "~{OUT9}_P$14") (pintype "bidirectional"))
    )
    (net (code "212") (name "unconnected-(U14-~{OUT10}-PadP$15)") (class "Default")
      (node (ref "U14") (pin "P$15") (pinfunction "~{OUT10}_P$15") (pintype "bidirectional"))
    )
    (net (code "213") (name "unconnected-(U14-~{OUT11}-PadP$16)") (class "Default")
      (node (ref "U14") (pin "P$16") (pinfunction "~{OUT11}_P$16") (pintype "bidirectional"))
    )
    (net (code "214") (name "unconnected-(U14-~{OUT12}-PadP$17)") (class "Default")
      (node (ref "U14") (pin "P$17") (pinfunction "~{OUT12}_P$17") (pintype "bidirectional"))
    )
    (net (code "215") (name "unconnected-(U14-~{OUT13}-PadP$18)") (class "Default")
      (node (ref "U14") (pin "P$18") (pinfunction "~{OUT13}_P$18") (pintype "bidirectional"))
    )
    (net (code "216") (name "unconnected-(U14-~{OUT14}-PadP$19)") (class "Default")
      (node (ref "U14") (pin "P$19") (pinfunction "~{OUT14}_P$19") (pintype "bidirectional"))
    )
    (net (code "217") (name "unconnected-(U14-~{OUT15}-PadP$20)") (class "Default")
      (node (ref "U14") (pin "P$20") (pinfunction "~{OUT15}_P$20") (pintype "bidirectional"))
    )
  )
)
